# TeensySensor20250629.net
KiCad netlist of a schematic drawn in EasyEDA Pro
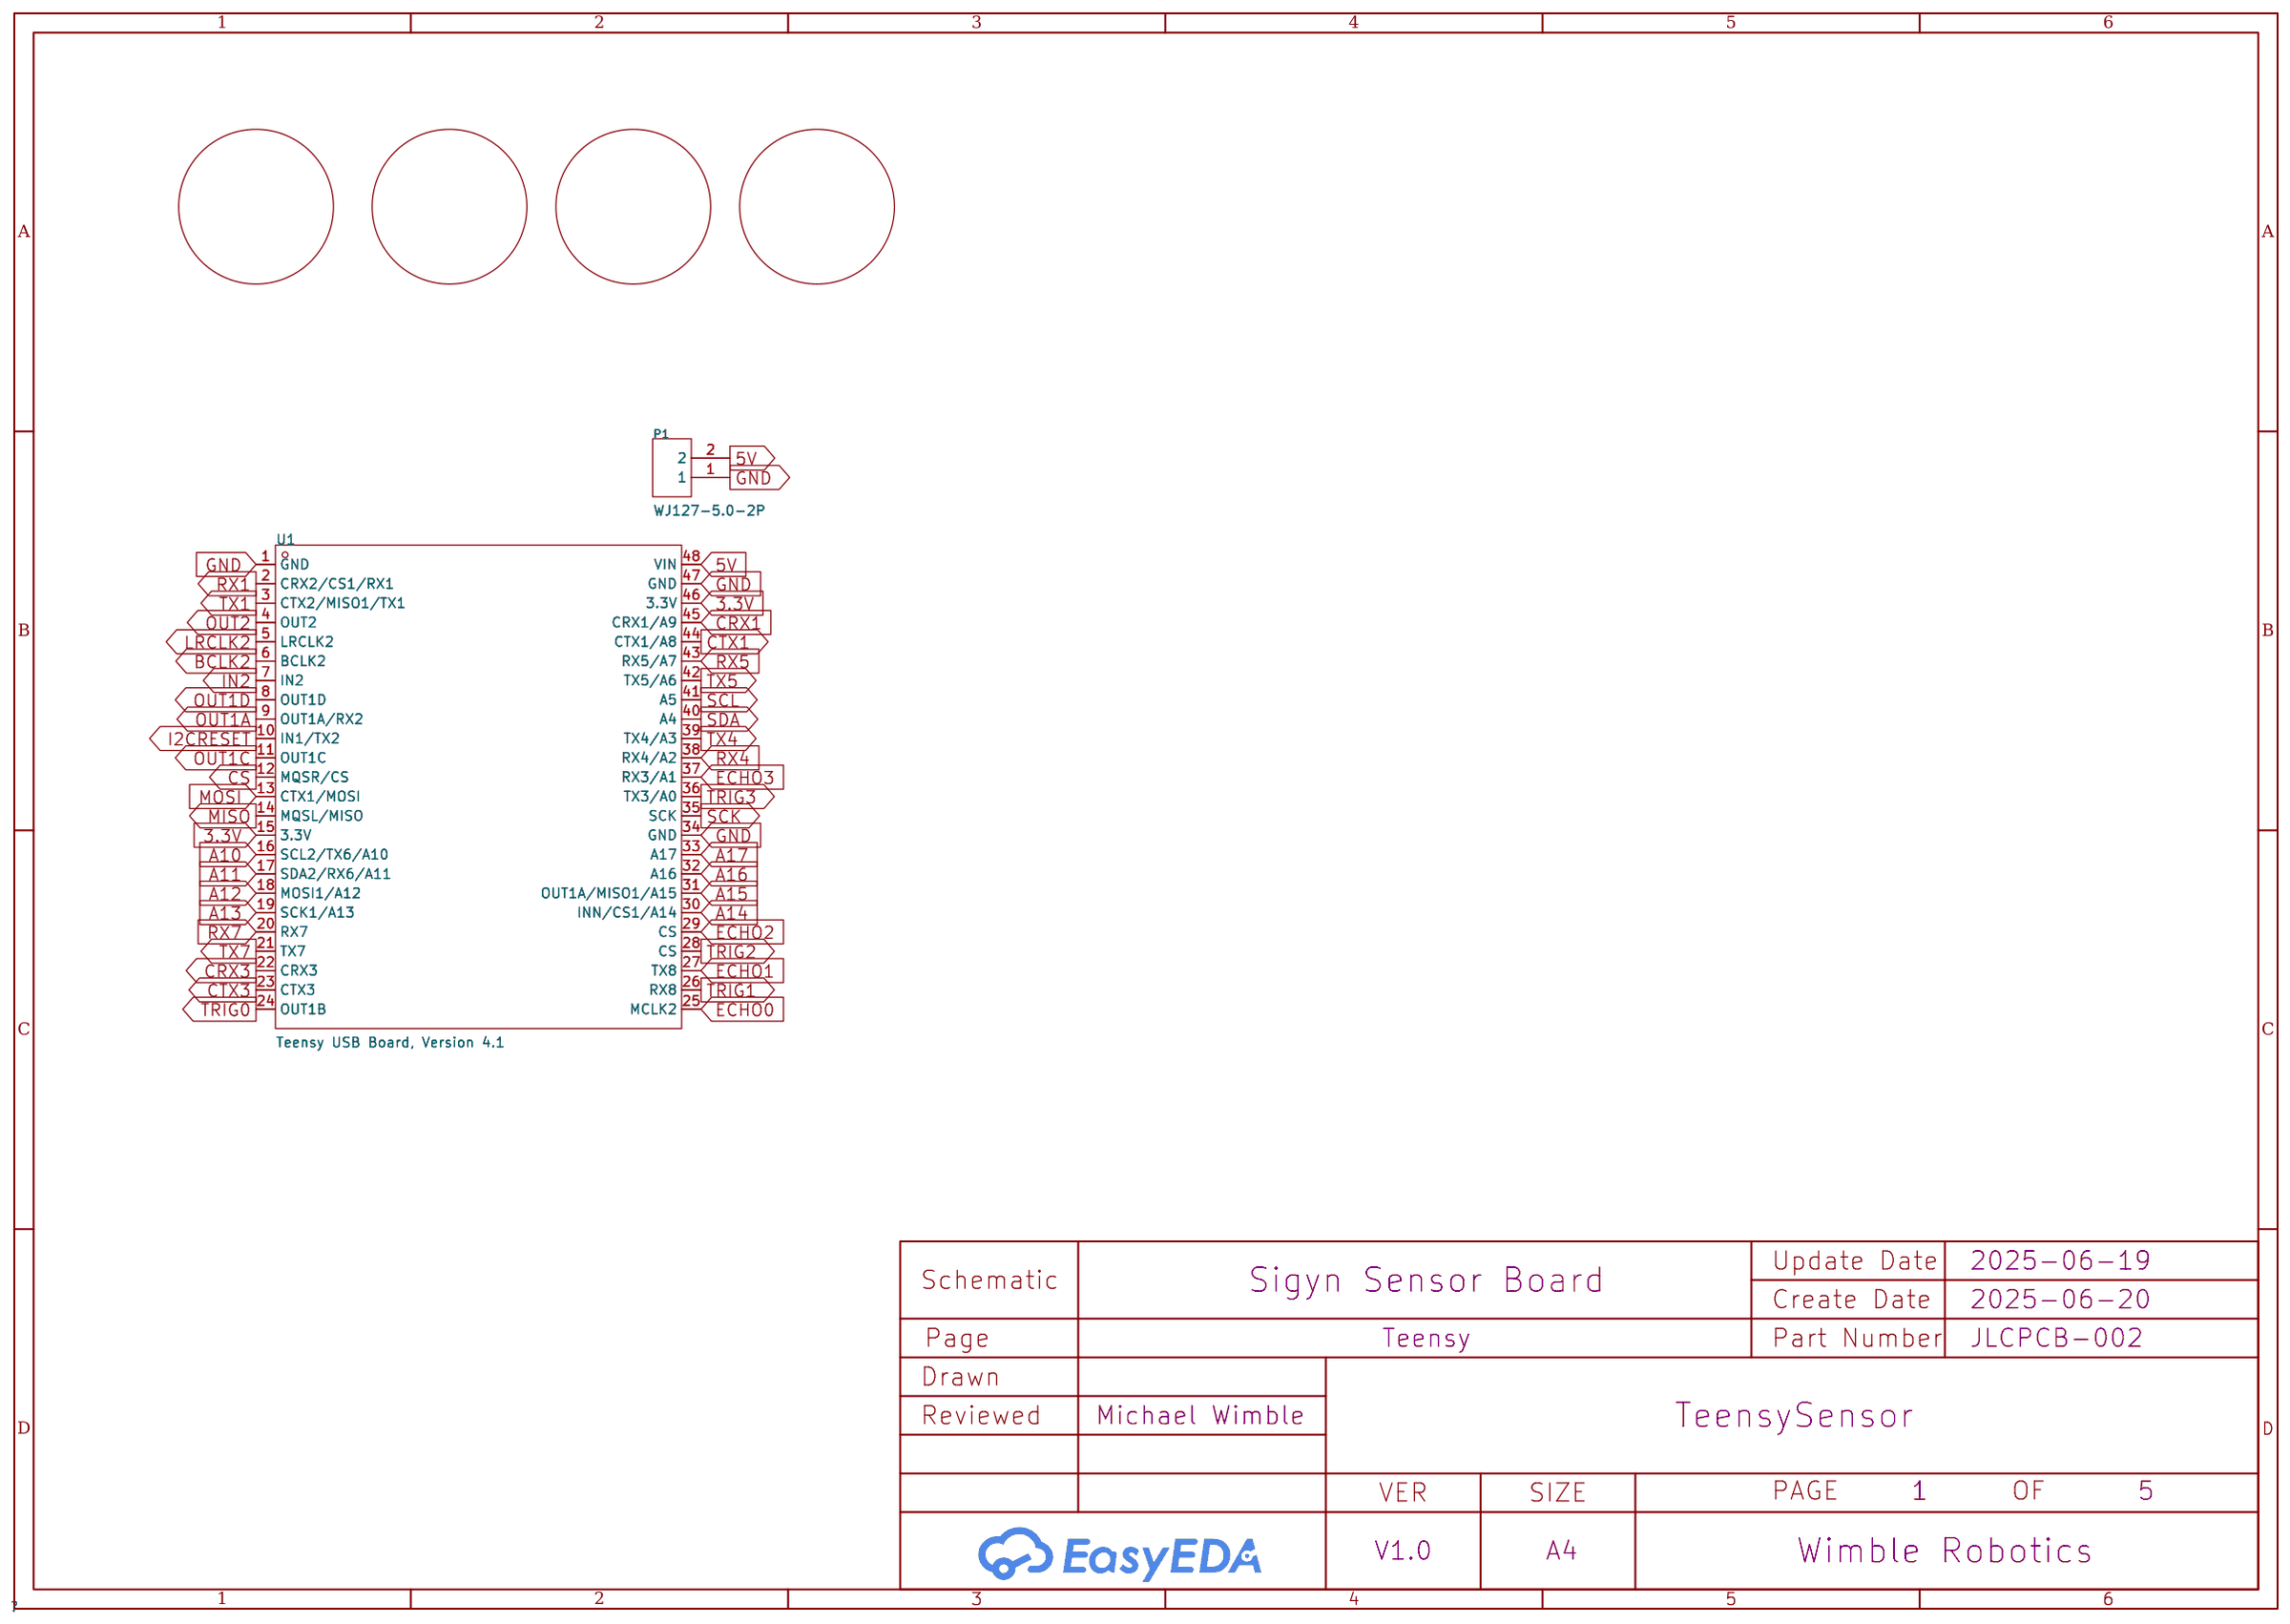
[diagram p0: Teensy]
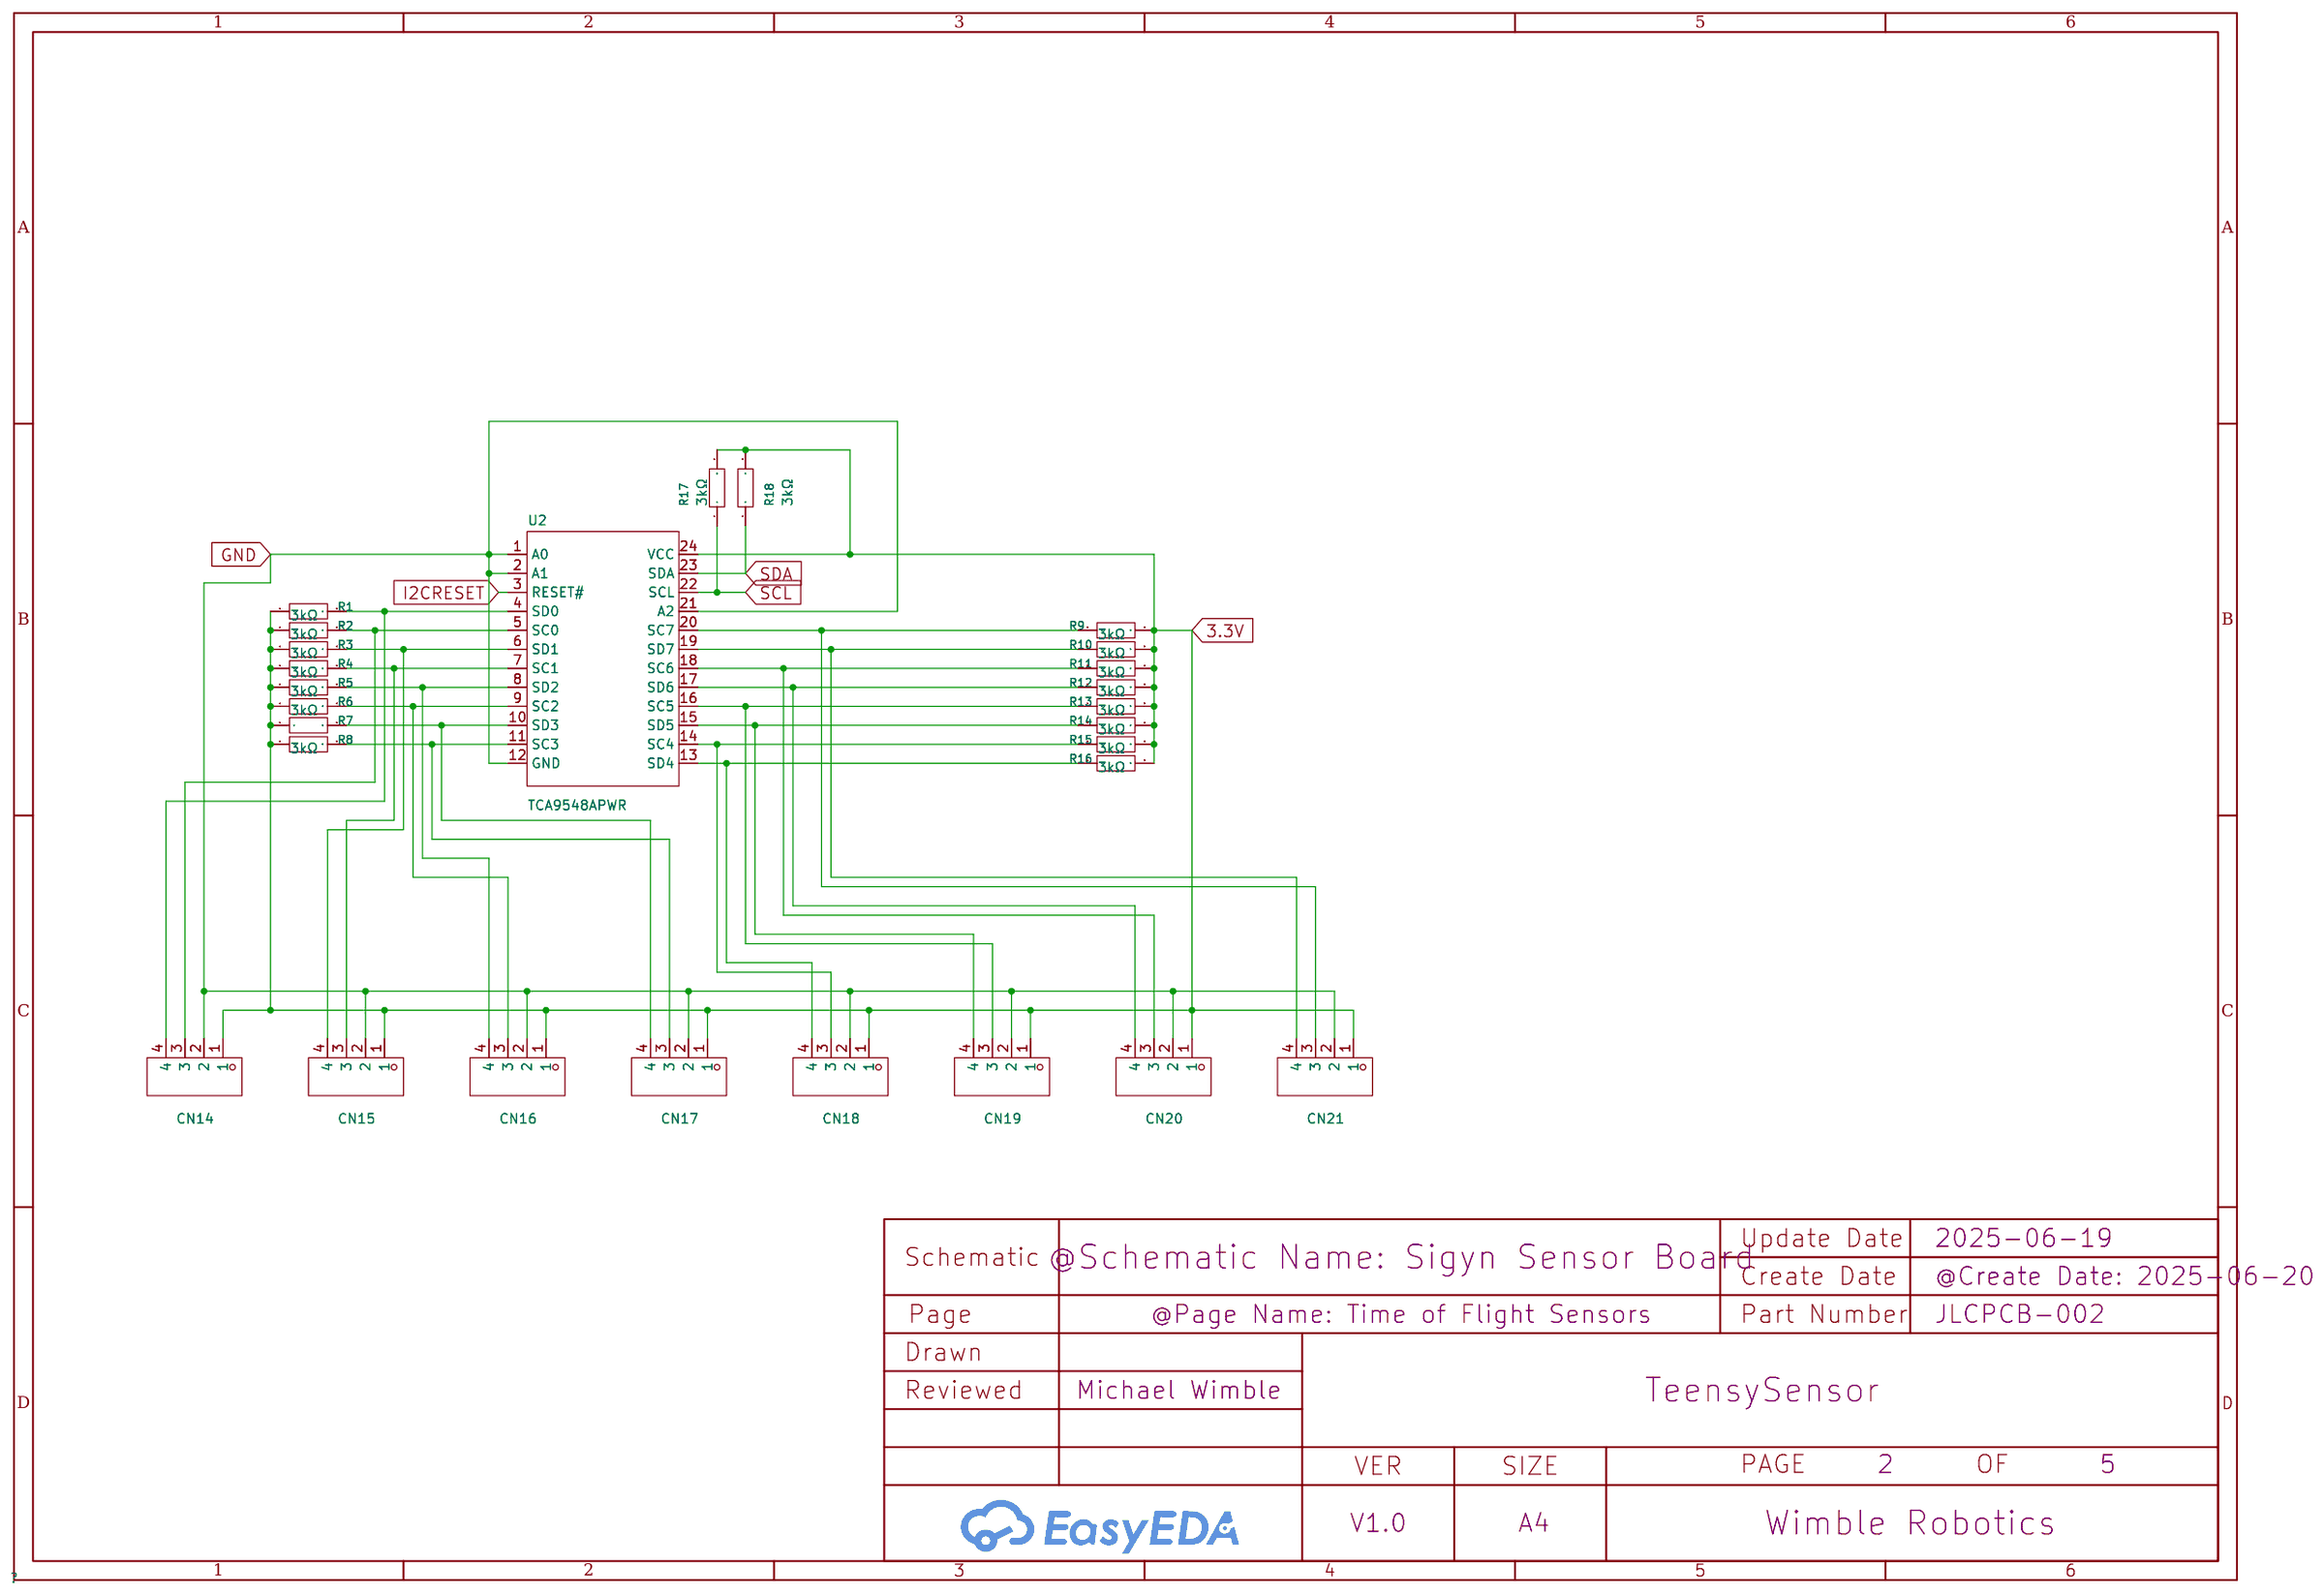
[diagram p1: Time of Flight Sensors]
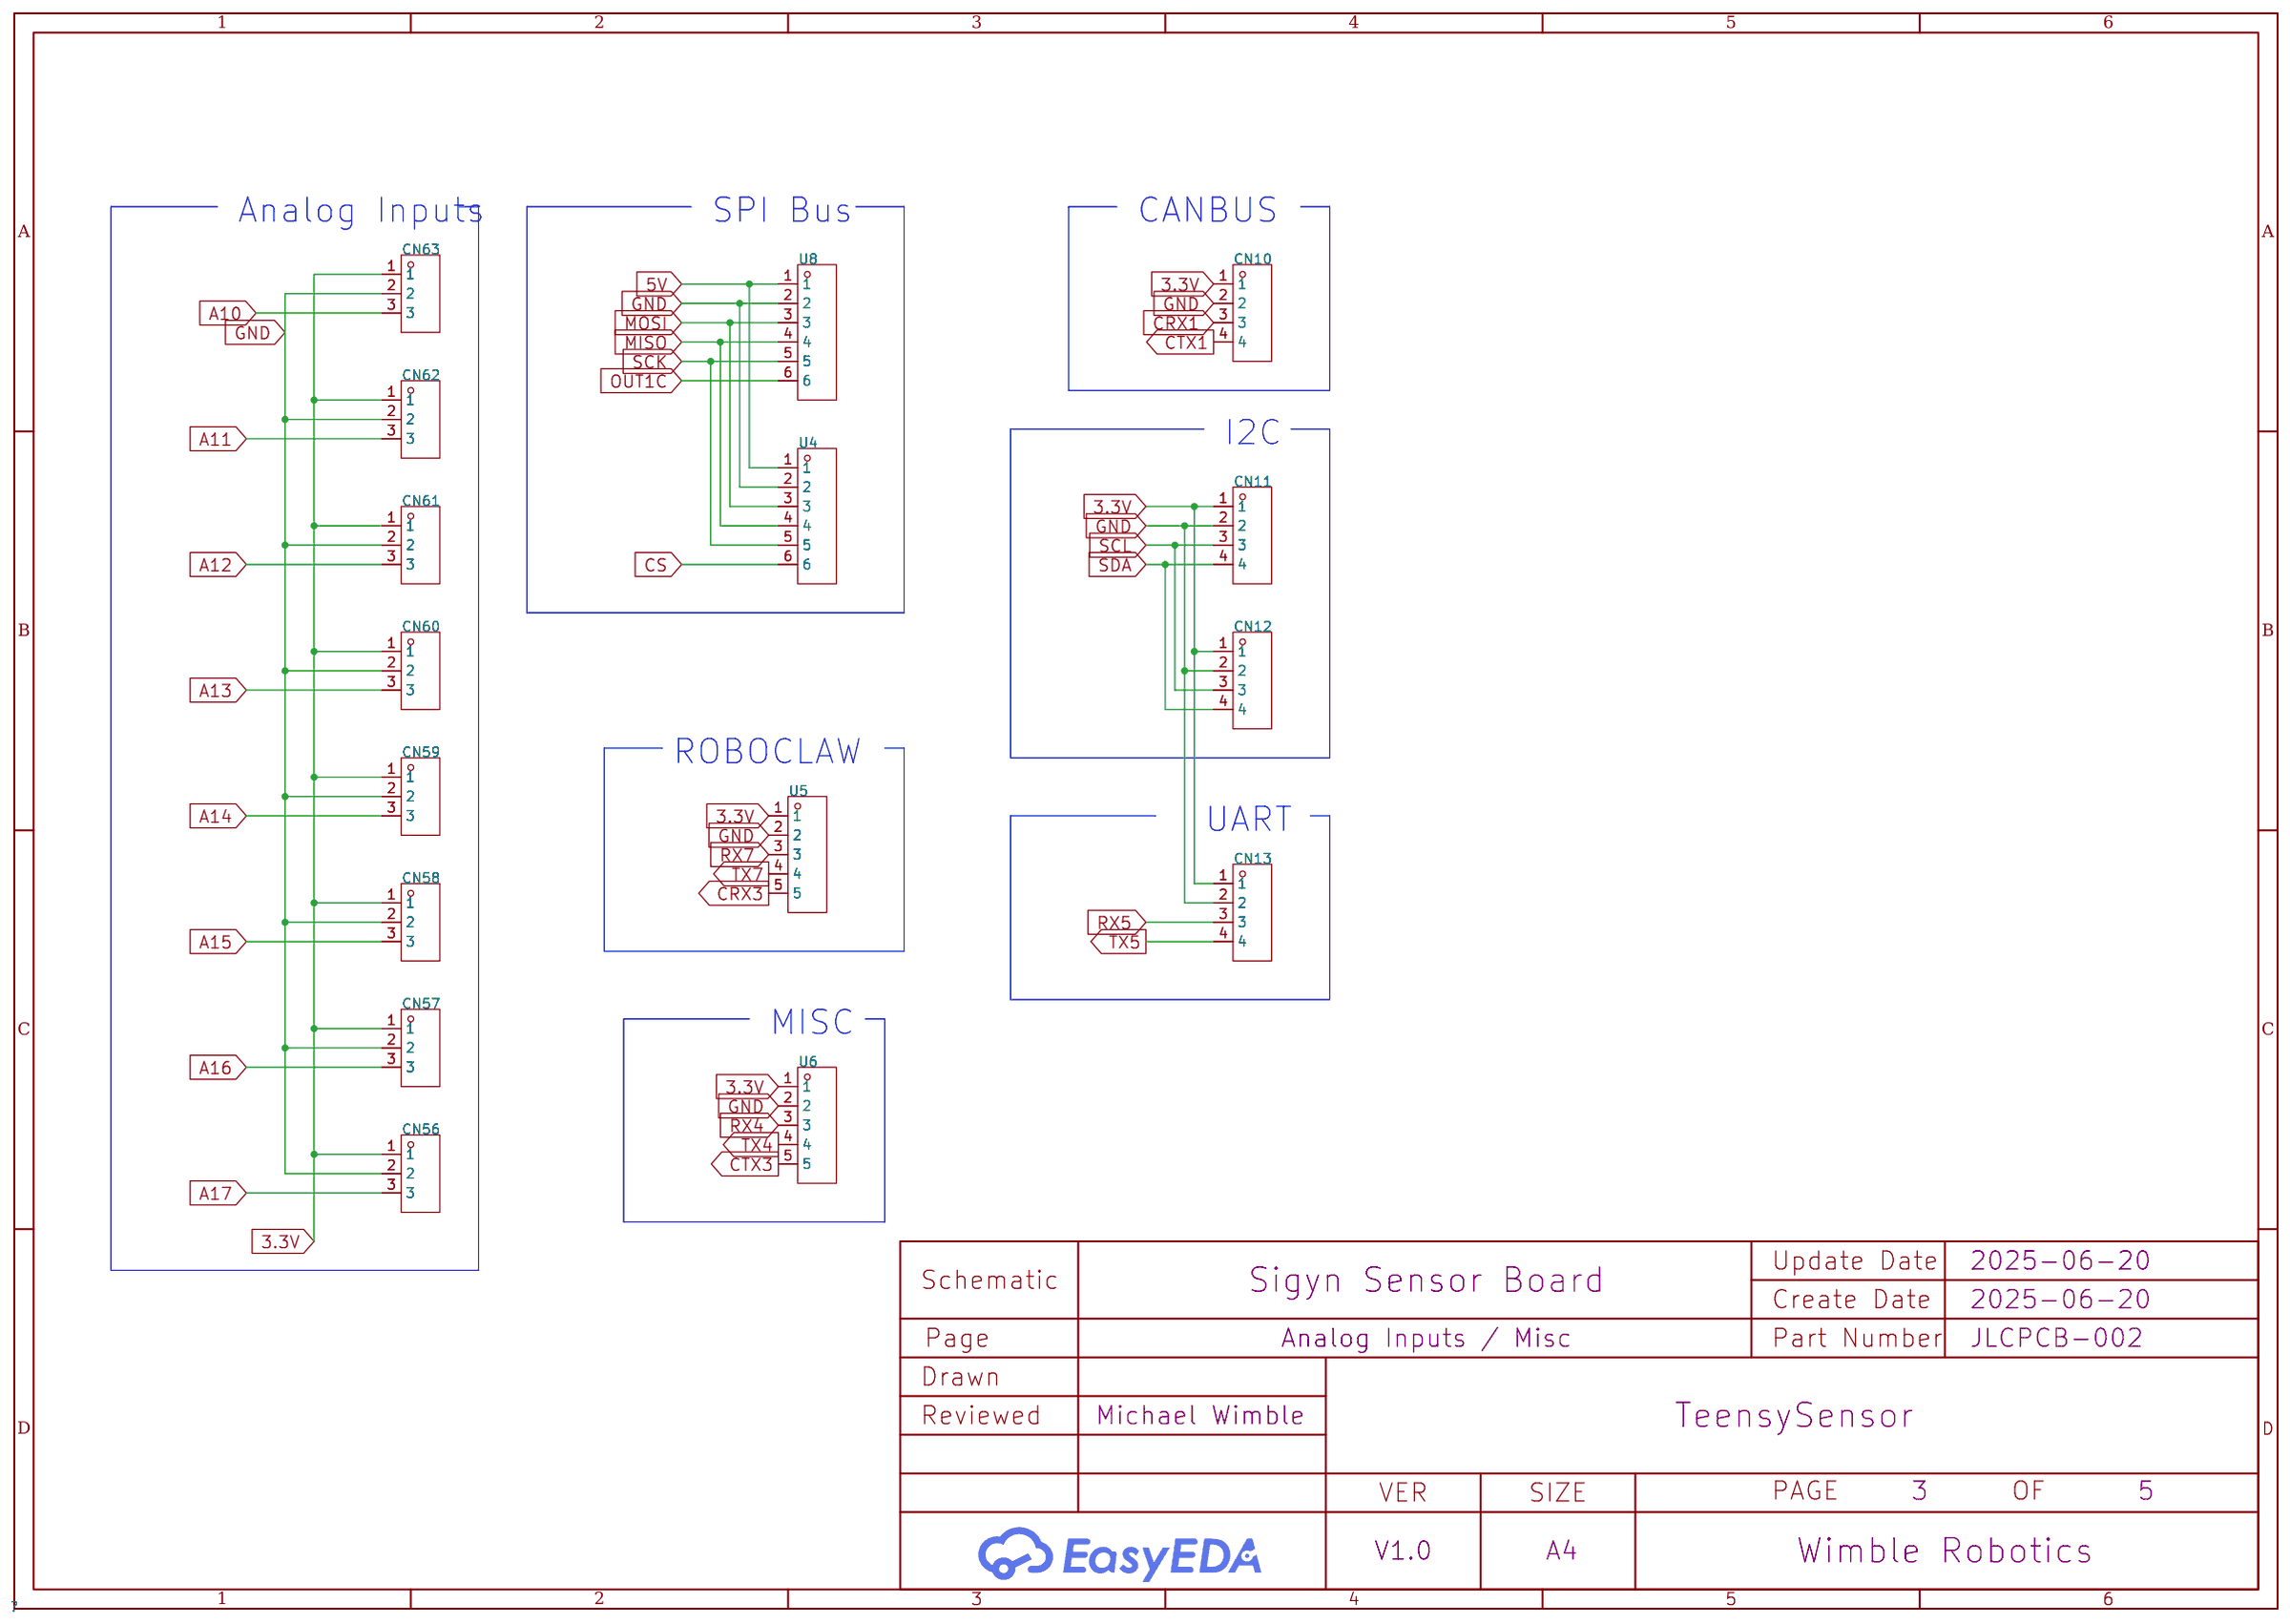
[diagram p2: Analog Inputs / Misc]
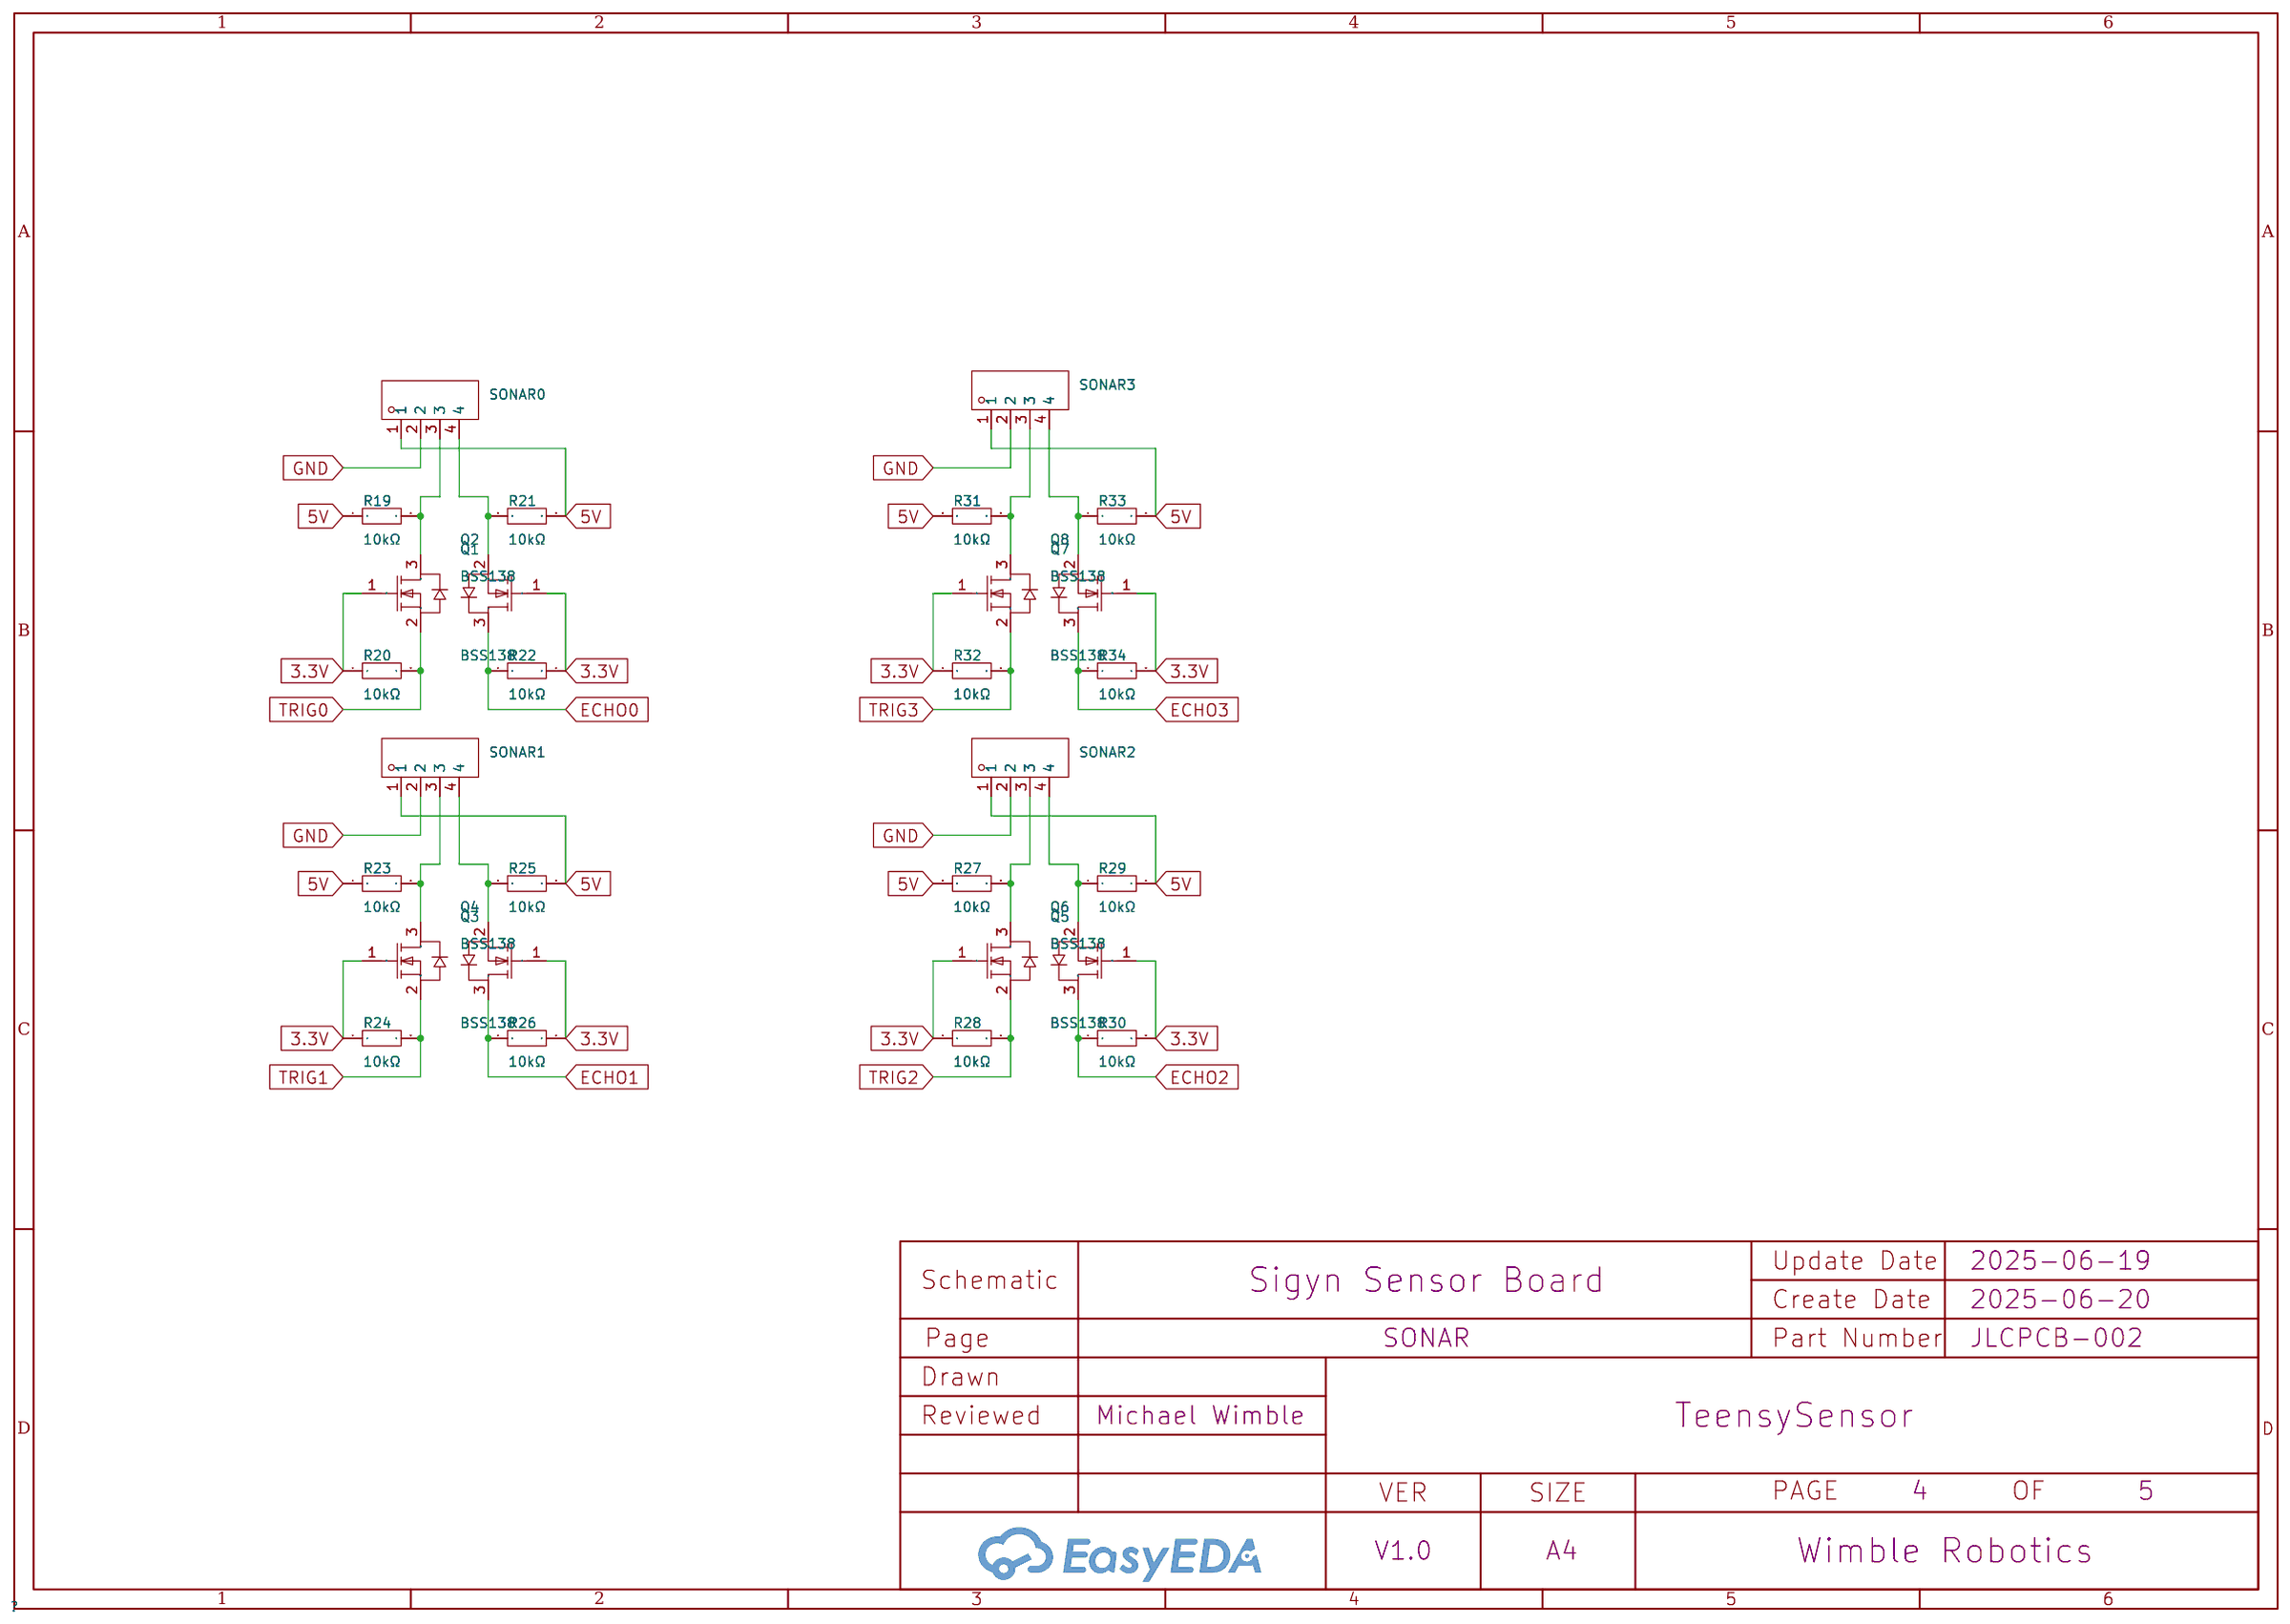
[diagram p3: SONAR]
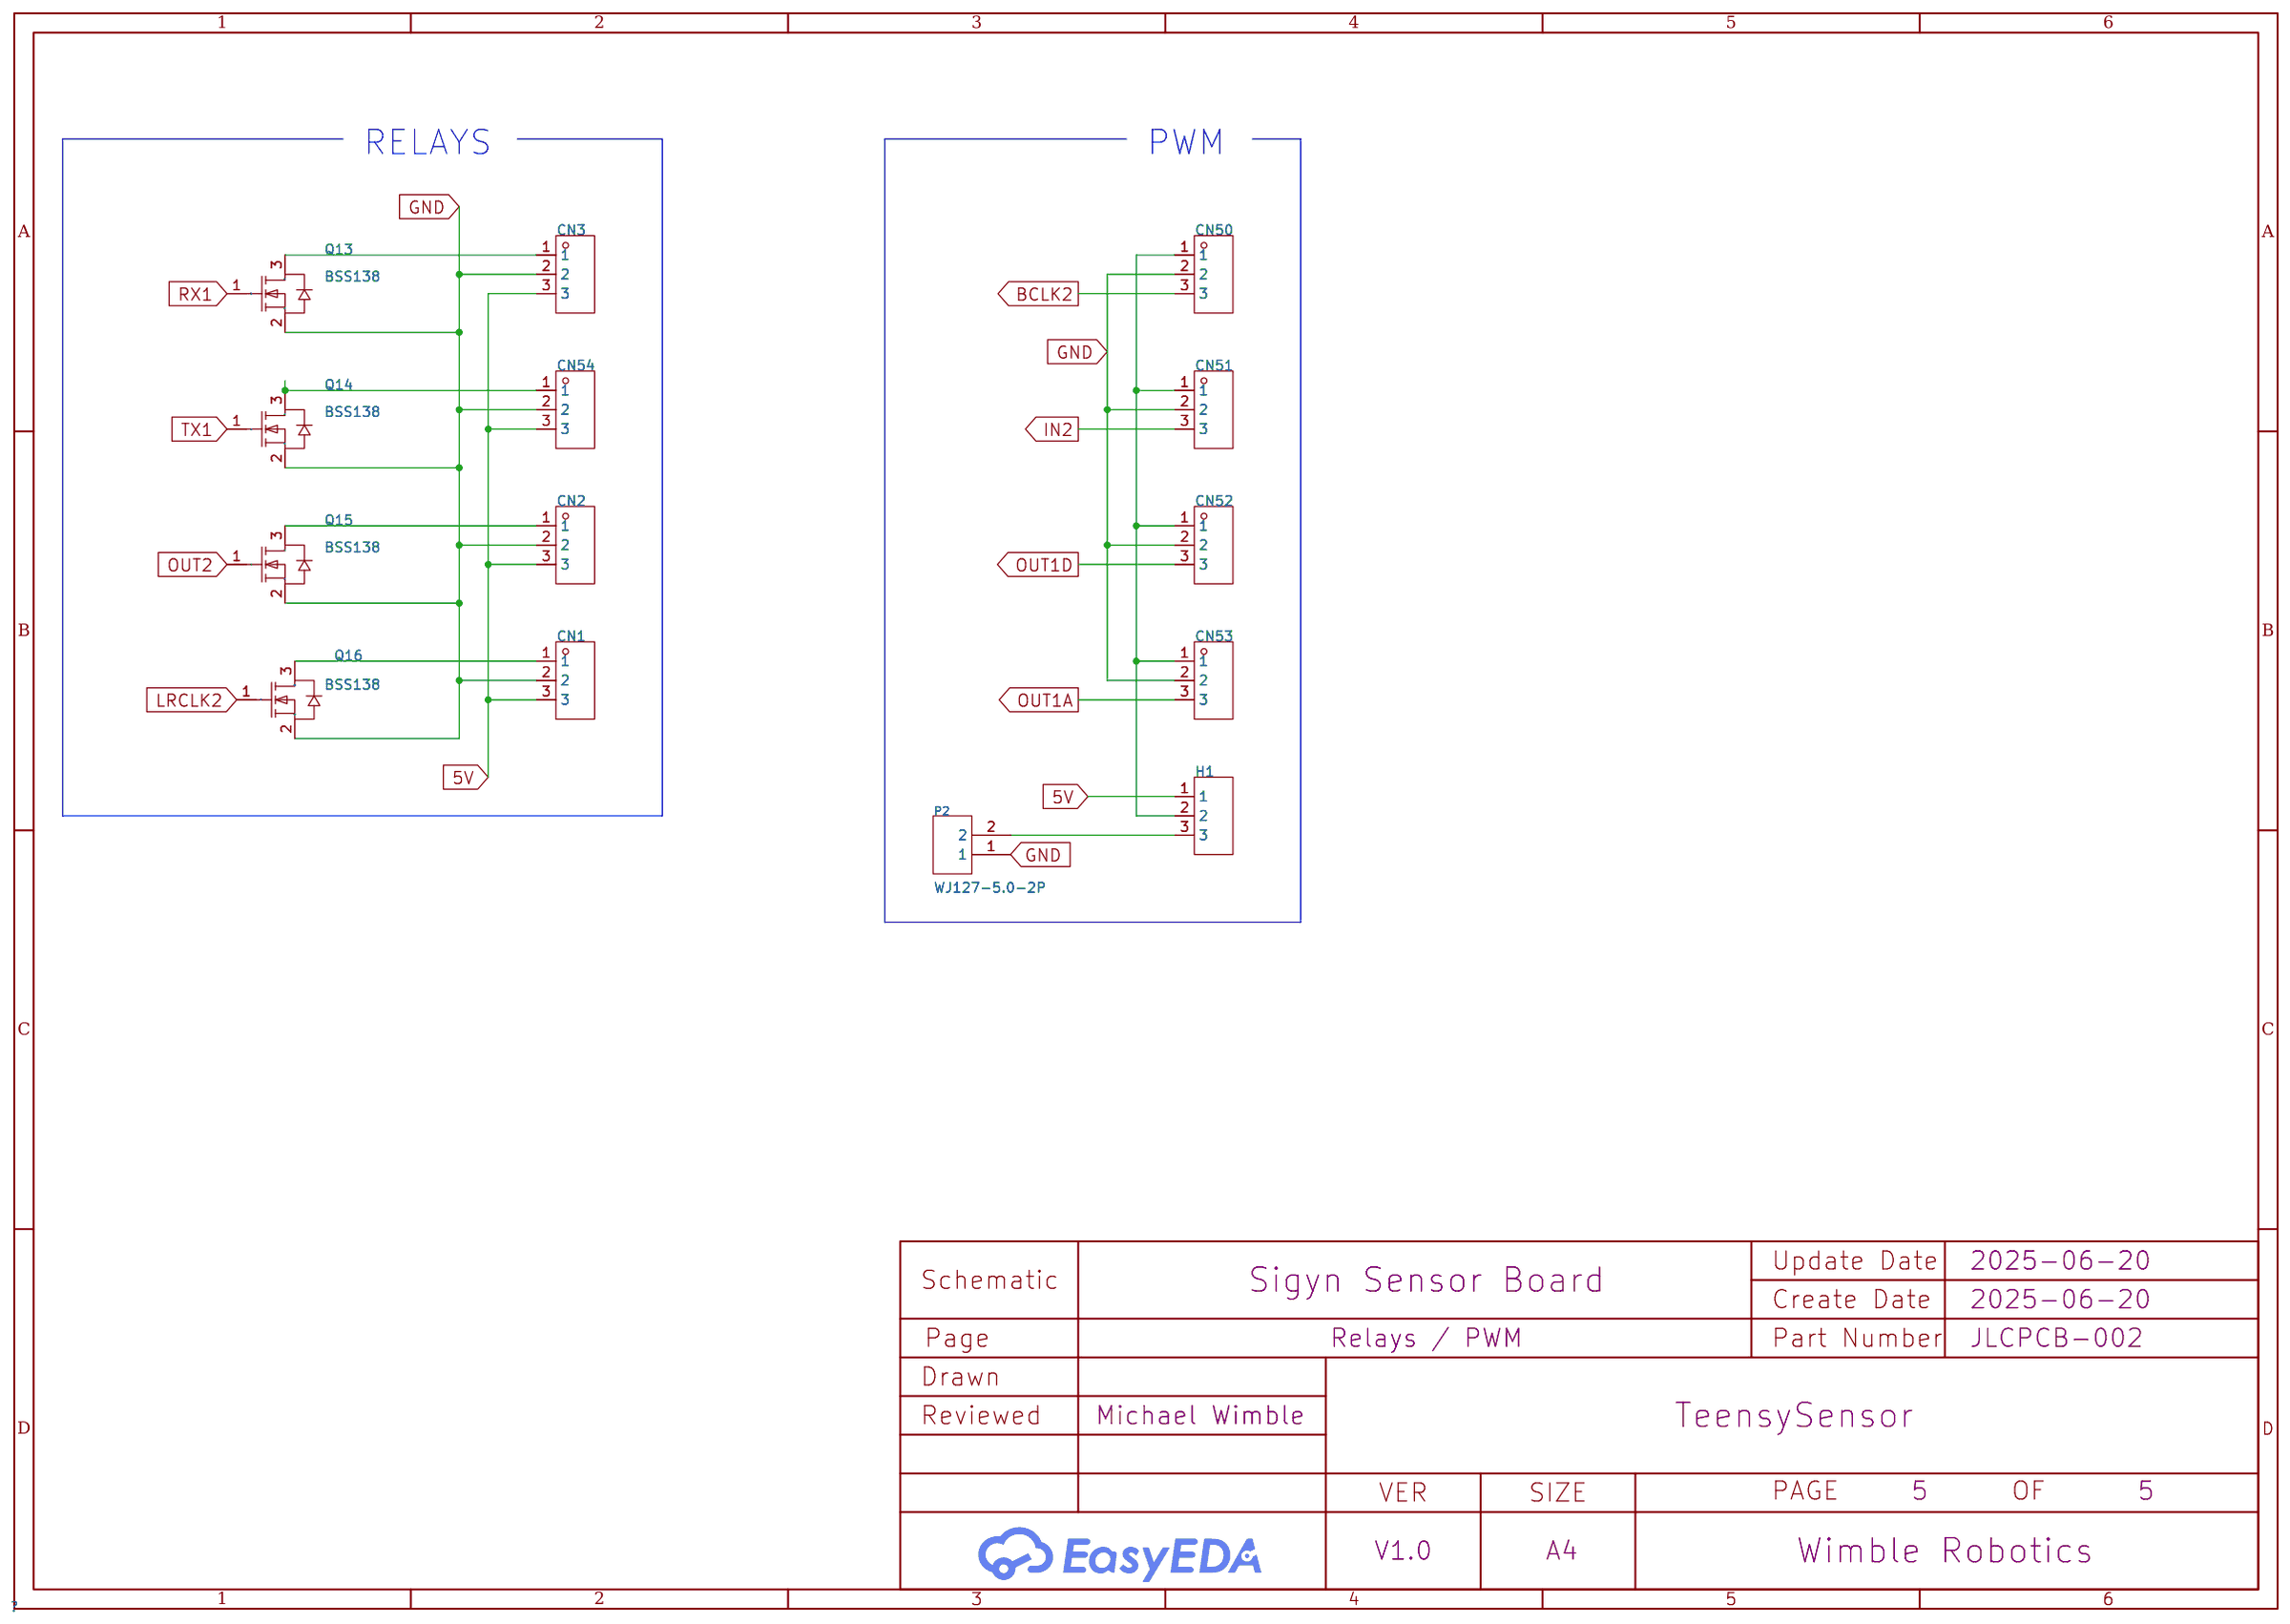
[diagram p4: Relays / PWM]

(export (version "E")
  (design (tool "Eeschema 10.0.6"))
  (components
    (comp (ref "P1")
      (value "WJ127-5.0-2P")
      (footprint "easyedapro:CONN-TH_2P-P5.00_CPC3703CTR")
      (fields (field (name "Manufacturer") "KANGNEX(康奈克斯电气)"))
      (libsource (lib "easyedapro") (part "WJ127-5.0-2P"))
    )
    (comp (ref "U1")
      (value "Teensy USB Board, Version 4.1")
      (footprint "easyedapro:COMM-TH_L61.0-W17.8-P2.54")
      (libsource (lib "easyedapro") (part "TEENSY USB BOARD, VERSION 4.1"))
    )
    (comp (ref "U12")
      (value "~")
      (footprint "easyedapro:3.5mm_Hole")
      (description "Mounting hole")
      (libsource (lib "easyedapro") (part "3.5MMHole"))
    )
    (comp (ref "U13")
      (value "~")
      (footprint "easyedapro:3.5mm_Hole")
      (description "Mounting hole")
      (libsource (lib "easyedapro") (part "3.5MMHole"))
    )
    (comp (ref "U14")
      (value "~")
      (footprint "easyedapro:3.5mm_Hole")
      (description "Mounting hole")
      (libsource (lib "easyedapro") (part "3.5MMHole"))
    )
    (comp (ref "U15")
      (value "~")
      (footprint "easyedapro:3.5mm_Hole")
      (description "Mounting hole")
      (libsource (lib "easyedapro") (part "3.5MMHole"))
    )
    (comp (ref "CN14")
      (value "ZX-XH2.54-4PZZ")
      (footprint "easyedapro:CONN-TH_4P-P2.50_4PIN")
      (fields (field (name "Manufacturer") "Megastar(兆星)"))
      (libsource (lib "easyedapro") (part "ZX-XH2.54-4PZZ"))
    )
    (comp (ref "CN15")
      (value "ZX-XH2.54-4PZZ")
      (footprint "easyedapro:CONN-TH_4P-P2.50_4PIN")
      (fields (field (name "Manufacturer") "Megastar(兆星)"))
      (libsource (lib "easyedapro") (part "ZX-XH2.54-4PZZ"))
    )
    (comp (ref "CN16")
      (value "ZX-XH2.54-4PZZ")
      (footprint "easyedapro:CONN-TH_4P-P2.50_4PIN")
      (fields (field (name "Manufacturer") "Megastar(兆星)"))
      (libsource (lib "easyedapro") (part "ZX-XH2.54-4PZZ"))
    )
    (comp (ref "CN17")
      (value "ZX-XH2.54-4PZZ")
      (footprint "easyedapro:CONN-TH_4P-P2.50_4PIN")
      (fields (field (name "Manufacturer") "Megastar(兆星)"))
      (libsource (lib "easyedapro") (part "ZX-XH2.54-4PZZ"))
    )
    (comp (ref "CN18")
      (value "ZX-XH2.54-4PZZ")
      (footprint "easyedapro:CONN-TH_4P-P2.50_4PIN")
      (fields (field (name "Manufacturer") "Megastar(兆星)"))
      (libsource (lib "easyedapro") (part "ZX-XH2.54-4PZZ"))
    )
    (comp (ref "CN19")
      (value "ZX-XH2.54-4PZZ")
      (footprint "easyedapro:CONN-TH_4P-P2.50_4PIN")
      (fields (field (name "Manufacturer") "Megastar(兆星)"))
      (libsource (lib "easyedapro") (part "ZX-XH2.54-4PZZ"))
    )
    (comp (ref "CN20")
      (value "ZX-XH2.54-4PZZ")
      (footprint "easyedapro:CONN-TH_4P-P2.50_4PIN")
      (fields (field (name "Manufacturer") "Megastar(兆星)"))
      (libsource (lib "easyedapro") (part "ZX-XH2.54-4PZZ"))
    )
    (comp (ref "CN21")
      (value "ZX-XH2.54-4PZZ")
      (footprint "easyedapro:CONN-TH_4P-P2.50_4PIN")
      (fields (field (name "Manufacturer") "Megastar(兆星)"))
      (libsource (lib "easyedapro") (part "ZX-XH2.54-4PZZ"))
    )
    (comp (ref "R1")
      (value "3kΩ")
      (footprint "easyedapro:R0603")
      (fields
        (field (name "Manufacturer Part") "0603WAF3001T5E")
        (field (name "Manufacturer") "UNI-ROYAL(厚声)")
      )
      (libsource (lib "easyedapro") (part "0603WAF3001T5E"))
    )
    (comp (ref "R2")
      (value "3kΩ")
      (footprint "easyedapro:R0603")
      (fields
        (field (name "Manufacturer Part") "0603WAF3001T5E")
        (field (name "Manufacturer") "UNI-ROYAL(厚声)")
      )
      (libsource (lib "easyedapro") (part "0603WAF3001T5E"))
    )
    (comp (ref "R3")
      (value "3kΩ")
      (footprint "easyedapro:R0603")
      (fields
        (field (name "Manufacturer Part") "0603WAF3001T5E")
        (field (name "Manufacturer") "UNI-ROYAL(厚声)")
      )
      (libsource (lib "easyedapro") (part "0603WAF3001T5E"))
    )
    (comp (ref "R4")
      (value "3kΩ")
      (footprint "easyedapro:R0603")
      (fields
        (field (name "Manufacturer Part") "0603WAF3001T5E")
        (field (name "Manufacturer") "UNI-ROYAL(厚声)")
      )
      (libsource (lib "easyedapro") (part "0603WAF3001T5E"))
    )
    (comp (ref "R5")
      (value "3kΩ")
      (footprint "easyedapro:R0603")
      (fields
        (field (name "Manufacturer Part") "0603WAF3001T5E")
        (field (name "Manufacturer") "UNI-ROYAL(厚声)")
      )
      (libsource (lib "easyedapro") (part "0603WAF3001T5E"))
    )
    (comp (ref "R6")
      (value "3kΩ")
      (footprint "easyedapro:R0603")
      (fields
        (field (name "Manufacturer Part") "0603WAF3001T5E")
        (field (name "Manufacturer") "UNI-ROYAL(厚声)")
      )
      (libsource (lib "easyedapro") (part "0603WAF3001T5E"))
    )
    (comp (ref "R7")
      (value "3kΩ")
      (footprint "easyedapro:R0603")
      (fields
        (field (name "Manufacturer Part") "0603WAF3001T5E")
        (field (name "Manufacturer") "UNI-ROYAL(厚声)")
      )
      (libsource (lib "easyedapro") (part "0603WAF3001T5E"))
    )
    (comp (ref "R8")
      (value "3kΩ")
      (footprint "easyedapro:R0603")
      (fields
        (field (name "Manufacturer Part") "0603WAF3001T5E")
        (field (name "Manufacturer") "UNI-ROYAL(厚声)")
      )
      (libsource (lib "easyedapro") (part "0603WAF3001T5E"))
    )
    (comp (ref "R9")
      (value "3kΩ")
      (footprint "easyedapro:R0603")
      (fields
        (field (name "Manufacturer Part") "0603WAF3001T5E")
        (field (name "Manufacturer") "UNI-ROYAL(厚声)")
      )
      (libsource (lib "easyedapro") (part "0603WAF3001T5E"))
    )
    (comp (ref "R10")
      (value "3kΩ")
      (footprint "easyedapro:R0603")
      (fields
        (field (name "Manufacturer Part") "0603WAF3001T5E")
        (field (name "Manufacturer") "UNI-ROYAL(厚声)")
      )
      (libsource (lib "easyedapro") (part "0603WAF3001T5E"))
    )
    (comp (ref "R11")
      (value "3kΩ")
      (footprint "easyedapro:R0603")
      (fields
        (field (name "Manufacturer Part") "0603WAF3001T5E")
        (field (name "Manufacturer") "UNI-ROYAL(厚声)")
      )
      (libsource (lib "easyedapro") (part "0603WAF3001T5E"))
    )
    (comp (ref "R12")
      (value "3kΩ")
      (footprint "easyedapro:R0603")
      (fields
        (field (name "Manufacturer Part") "0603WAF3001T5E")
        (field (name "Manufacturer") "UNI-ROYAL(厚声)")
      )
      (libsource (lib "easyedapro") (part "0603WAF3001T5E"))
    )
    (comp (ref "R13")
      (value "3kΩ")
      (footprint "easyedapro:R0603")
      (fields
        (field (name "Manufacturer Part") "0603WAF3001T5E")
        (field (name "Manufacturer") "UNI-ROYAL(厚声)")
      )
      (libsource (lib "easyedapro") (part "0603WAF3001T5E"))
    )
    (comp (ref "R14")
      (value "3kΩ")
      (footprint "easyedapro:R0603")
      (fields
        (field (name "Manufacturer Part") "0603WAF3001T5E")
        (field (name "Manufacturer") "UNI-ROYAL(厚声)")
      )
      (libsource (lib "easyedapro") (part "0603WAF3001T5E"))
    )
    (comp (ref "R15")
      (value "3kΩ")
      (footprint "easyedapro:R0603")
      (fields
        (field (name "Manufacturer Part") "0603WAF3001T5E")
        (field (name "Manufacturer") "UNI-ROYAL(厚声)")
      )
      (libsource (lib "easyedapro") (part "0603WAF3001T5E"))
    )
    (comp (ref "R16")
      (value "3kΩ")
      (footprint "easyedapro:R0603")
      (fields
        (field (name "Manufacturer Part") "0603WAF3001T5E")
        (field (name "Manufacturer") "UNI-ROYAL(厚声)")
      )
      (libsource (lib "easyedapro") (part "0603WAF3001T5E"))
    )
    (comp (ref "R17")
      (value "3kΩ")
      (footprint "easyedapro:R0603")
      (fields
        (field (name "Manufacturer Part") "0603WAF3001T5E")
        (field (name "Manufacturer") "UNI-ROYAL(厚声)")
      )
      (libsource (lib "easyedapro") (part "0603WAF3001T5E"))
    )
    (comp (ref "R18")
      (value "3kΩ")
      (footprint "easyedapro:R0603")
      (fields
        (field (name "Manufacturer Part") "0603WAF3001T5E")
        (field (name "Manufacturer") "UNI-ROYAL(厚声)")
      )
      (libsource (lib "easyedapro") (part "0603WAF3001T5E"))
    )
    (comp (ref "U2")
      (value "TCA9548APWR")
      (footprint "easyedapro:TSSOP-24_L7.8-W4.4-P0.65-LS6.4-BL")
      (fields (field (name "Manufacturer") "TI(德州仪器)"))
      (libsource (lib "easyedapro") (part "TCA9548APWR"))
    )
    (comp (ref "CN10")
      (value "ZX-XH2.54-4PZZ")
      (footprint "easyedapro:CONN-TH_4P-P2.50_4PIN")
      (fields (field (name "Manufacturer") "Megastar(兆星)"))
      (libsource (lib "easyedapro") (part "ZX-XH2.54-4PZZ"))
    )
    (comp (ref "CN11")
      (value "ZX-XH2.54-4PZZ")
      (footprint "easyedapro:CONN-TH_4P-P2.50_4PIN")
      (fields (field (name "Manufacturer") "Megastar(兆星)"))
      (libsource (lib "easyedapro") (part "ZX-XH2.54-4PZZ"))
    )
    (comp (ref "CN12")
      (value "ZX-XH2.54-4PZZ")
      (footprint "easyedapro:CONN-TH_4P-P2.50_4PIN")
      (fields (field (name "Manufacturer") "Megastar(兆星)"))
      (libsource (lib "easyedapro") (part "ZX-XH2.54-4PZZ"))
    )
    (comp (ref "CN13")
      (value "ZX-XH2.54-4PZZ")
      (footprint "easyedapro:CONN-TH_4P-P2.50_4PIN")
      (fields (field (name "Manufacturer") "Megastar(兆星)"))
      (libsource (lib "easyedapro") (part "ZX-XH2.54-4PZZ"))
    )
    (comp (ref "CN56")
      (value "ZX-XH2.54-3PZZ")
      (footprint "easyedapro:CONN-TH_3P-P2.54_2501S-3P")
      (fields (field (name "Manufacturer") "Megastar(兆星)"))
      (libsource (lib "easyedapro") (part "ZX-XH2.54-3PZZ"))
    )
    (comp (ref "CN57")
      (value "ZX-XH2.54-3PZZ")
      (footprint "easyedapro:CONN-TH_3P-P2.54_2501S-3P")
      (fields (field (name "Manufacturer") "Megastar(兆星)"))
      (libsource (lib "easyedapro") (part "ZX-XH2.54-3PZZ"))
    )
    (comp (ref "CN58")
      (value "ZX-XH2.54-3PZZ")
      (footprint "easyedapro:CONN-TH_3P-P2.54_2501S-3P")
      (fields (field (name "Manufacturer") "Megastar(兆星)"))
      (libsource (lib "easyedapro") (part "ZX-XH2.54-3PZZ"))
    )
    (comp (ref "CN59")
      (value "ZX-XH2.54-3PZZ")
      (footprint "easyedapro:CONN-TH_3P-P2.54_2501S-3P")
      (fields (field (name "Manufacturer") "Megastar(兆星)"))
      (libsource (lib "easyedapro") (part "ZX-XH2.54-3PZZ"))
    )
    (comp (ref "CN60")
      (value "ZX-XH2.54-3PZZ")
      (footprint "easyedapro:CONN-TH_3P-P2.54_2501S-3P")
      (fields (field (name "Manufacturer") "Megastar(兆星)"))
      (libsource (lib "easyedapro") (part "ZX-XH2.54-3PZZ"))
    )
    (comp (ref "CN61")
      (value "ZX-XH2.54-3PZZ")
      (footprint "easyedapro:CONN-TH_3P-P2.54_2501S-3P")
      (fields (field (name "Manufacturer") "Megastar(兆星)"))
      (libsource (lib "easyedapro") (part "ZX-XH2.54-3PZZ"))
    )
    (comp (ref "CN62")
      (value "ZX-XH2.54-3PZZ")
      (footprint "easyedapro:CONN-TH_3P-P2.54_2501S-3P")
      (fields (field (name "Manufacturer") "Megastar(兆星)"))
      (libsource (lib "easyedapro") (part "ZX-XH2.54-3PZZ"))
    )
    (comp (ref "CN63")
      (value "ZX-XH2.54-3PZZ")
      (footprint "easyedapro:CONN-TH_3P-P2.54_2501S-3P")
      (fields (field (name "Manufacturer") "Megastar(兆星)"))
      (libsource (lib "easyedapro") (part "ZX-XH2.54-3PZZ"))
    )
    (comp (ref "U4")
      (value "ZX-XH2.54-6PZZ")
      (footprint "easyedapro:CONN-TH_6P-P2.50_ZX-XH2.54-6PZZ")
      (fields (field (name "Manufacturer") "Megastar(兆星)"))
      (libsource (lib "easyedapro") (part "ZX-XH2.54-6PZZ"))
    )
    (comp (ref "U5")
      (value "ZX-XH2.54-5PZZ")
      (footprint "easyedapro:CONN-TH_5P-P2.50_ZX-XH2.54-5PZZ")
      (fields (field (name "Manufacturer") "Megastar(兆星)"))
      (libsource (lib "easyedapro") (part "ZX-XH2.54-5PZZ"))
    )
    (comp (ref "U6")
      (value "ZX-XH2.54-5PZZ")
      (footprint "easyedapro:CONN-TH_5P-P2.50_ZX-XH2.54-5PZZ")
      (fields (field (name "Manufacturer") "Megastar(兆星)"))
      (libsource (lib "easyedapro") (part "ZX-XH2.54-5PZZ"))
    )
    (comp (ref "U8")
      (value "ZX-XH2.54-6PZZ")
      (footprint "easyedapro:CONN-TH_6P-P2.50_ZX-XH2.54-6PZZ")
      (fields (field (name "Manufacturer") "Megastar(兆星)"))
      (libsource (lib "easyedapro") (part "ZX-XH2.54-6PZZ"))
    )
    (comp (ref "Q1")
      (value "BSS138")
      (footprint "easyedapro:SOT-23-3_L2.9-W1.6-P1.90-LS2.8-BR")
      (fields (field (name "Manufacturer") "TECH PUBLIC(台舟)"))
      (libsource (lib "easyedapro") (part "BSS138_C18212695"))
    )
    (comp (ref "Q2")
      (value "BSS138")
      (footprint "easyedapro:SOT-23-3_L2.9-W1.6-P1.90-LS2.8-BR")
      (fields (field (name "Manufacturer") "TECH PUBLIC(台舟)"))
      (libsource (lib "easyedapro") (part "BSS138_C18212695"))
    )
    (comp (ref "Q3")
      (value "BSS138")
      (footprint "easyedapro:SOT-23-3_L2.9-W1.6-P1.90-LS2.8-BR")
      (fields (field (name "Manufacturer") "TECH PUBLIC(台舟)"))
      (libsource (lib "easyedapro") (part "BSS138_C18212695"))
    )
    (comp (ref "Q4")
      (value "BSS138")
      (footprint "easyedapro:SOT-23-3_L2.9-W1.6-P1.90-LS2.8-BR")
      (fields (field (name "Manufacturer") "TECH PUBLIC(台舟)"))
      (libsource (lib "easyedapro") (part "BSS138_C18212695"))
    )
    (comp (ref "Q5")
      (value "BSS138")
      (footprint "easyedapro:SOT-23-3_L2.9-W1.6-P1.90-LS2.8-BR")
      (fields (field (name "Manufacturer") "TECH PUBLIC(台舟)"))
      (libsource (lib "easyedapro") (part "BSS138_C18212695"))
    )
    (comp (ref "Q6")
      (value "BSS138")
      (footprint "easyedapro:SOT-23-3_L2.9-W1.6-P1.90-LS2.8-BR")
      (fields (field (name "Manufacturer") "TECH PUBLIC(台舟)"))
      (libsource (lib "easyedapro") (part "BSS138_C18212695"))
    )
    (comp (ref "Q7")
      (value "BSS138")
      (footprint "easyedapro:SOT-23-3_L2.9-W1.6-P1.90-LS2.8-BR")
      (fields (field (name "Manufacturer") "TECH PUBLIC(台舟)"))
      (libsource (lib "easyedapro") (part "BSS138_C18212695"))
    )
    (comp (ref "Q8")
      (value "BSS138")
      (footprint "easyedapro:SOT-23-3_L2.9-W1.6-P1.90-LS2.8-BR")
      (fields (field (name "Manufacturer") "TECH PUBLIC(台舟)"))
      (libsource (lib "easyedapro") (part "BSS138_C18212695"))
    )
    (comp (ref "R19")
      (value "10kΩ")
      (footprint "easyedapro:R0603")
      (fields (field (name "Manufacturer Part") "RC0603FR-0710KL") (field (name "Manufacturer") "YAGEO(国巨)"))
      (libsource (lib "easyedapro") (part "RC0603FR-0710KL"))
    )
    (comp (ref "R20")
      (value "10kΩ")
      (footprint "easyedapro:R0603")
      (fields (field (name "Manufacturer Part") "RC0603FR-0710KL") (field (name "Manufacturer") "YAGEO(国巨)"))
      (libsource (lib "easyedapro") (part "RC0603FR-0710KL"))
    )
    (comp (ref "R21")
      (value "10kΩ")
      (footprint "easyedapro:R0603")
      (fields (field (name "Manufacturer Part") "RC0603FR-0710KL") (field (name "Manufacturer") "YAGEO(国巨)"))
      (libsource (lib "easyedapro") (part "RC0603FR-0710KL"))
    )
    (comp (ref "R22")
      (value "10kΩ")
      (footprint "easyedapro:R0603")
      (fields (field (name "Manufacturer Part") "RC0603FR-0710KL") (field (name "Manufacturer") "YAGEO(国巨)"))
      (libsource (lib "easyedapro") (part "RC0603FR-0710KL"))
    )
    (comp (ref "R23")
      (value "10kΩ")
      (footprint "easyedapro:R0603")
      (fields (field (name "Manufacturer Part") "RC0603FR-0710KL") (field (name "Manufacturer") "YAGEO(国巨)"))
      (libsource (lib "easyedapro") (part "RC0603FR-0710KL"))
    )
    (comp (ref "R24")
      (value "10kΩ")
      (footprint "easyedapro:R0603")
      (fields (field (name "Manufacturer Part") "RC0603FR-0710KL") (field (name "Manufacturer") "YAGEO(国巨)"))
      (libsource (lib "easyedapro") (part "RC0603FR-0710KL"))
    )
    (comp (ref "R25")
      (value "10kΩ")
      (footprint "easyedapro:R0603")
      (fields (field (name "Manufacturer Part") "RC0603FR-0710KL") (field (name "Manufacturer") "YAGEO(国巨)"))
      (libsource (lib "easyedapro") (part "RC0603FR-0710KL"))
    )
    (comp (ref "R26")
      (value "10kΩ")
      (footprint "easyedapro:R0603")
      (fields (field (name "Manufacturer Part") "RC0603FR-0710KL") (field (name "Manufacturer") "YAGEO(国巨)"))
      (libsource (lib "easyedapro") (part "RC0603FR-0710KL"))
    )
    (comp (ref "R27")
      (value "10kΩ")
      (footprint "easyedapro:R0603")
      (fields (field (name "Manufacturer Part") "RC0603FR-0710KL") (field (name "Manufacturer") "YAGEO(国巨)"))
      (libsource (lib "easyedapro") (part "RC0603FR-0710KL"))
    )
    (comp (ref "R28")
      (value "10kΩ")
      (footprint "easyedapro:R0603")
      (fields (field (name "Manufacturer Part") "RC0603FR-0710KL") (field (name "Manufacturer") "YAGEO(国巨)"))
      (libsource (lib "easyedapro") (part "RC0603FR-0710KL"))
    )
    (comp (ref "R29")
      (value "10kΩ")
      (footprint "easyedapro:R0603")
      (fields (field (name "Manufacturer Part") "RC0603FR-0710KL") (field (name "Manufacturer") "YAGEO(国巨)"))
      (libsource (lib "easyedapro") (part "RC0603FR-0710KL"))
    )
    (comp (ref "R30")
      (value "10kΩ")
      (footprint "easyedapro:R0603")
      (fields (field (name "Manufacturer Part") "RC0603FR-0710KL") (field (name "Manufacturer") "YAGEO(国巨)"))
      (libsource (lib "easyedapro") (part "RC0603FR-0710KL"))
    )
    (comp (ref "R31")
      (value "10kΩ")
      (footprint "easyedapro:R0603")
      (fields (field (name "Manufacturer Part") "RC0603FR-0710KL") (field (name "Manufacturer") "YAGEO(国巨)"))
      (libsource (lib "easyedapro") (part "RC0603FR-0710KL"))
    )
    (comp (ref "R32")
      (value "10kΩ")
      (footprint "easyedapro:R0603")
      (fields (field (name "Manufacturer Part") "RC0603FR-0710KL") (field (name "Manufacturer") "YAGEO(国巨)"))
      (libsource (lib "easyedapro") (part "RC0603FR-0710KL"))
    )
    (comp (ref "R33")
      (value "10kΩ")
      (footprint "easyedapro:R0603")
      (fields (field (name "Manufacturer Part") "RC0603FR-0710KL") (field (name "Manufacturer") "YAGEO(国巨)"))
      (libsource (lib "easyedapro") (part "RC0603FR-0710KL"))
    )
    (comp (ref "R34")
      (value "10kΩ")
      (footprint "easyedapro:R0603")
      (fields (field (name "Manufacturer Part") "RC0603FR-0710KL") (field (name "Manufacturer") "YAGEO(国巨)"))
      (libsource (lib "easyedapro") (part "RC0603FR-0710KL"))
    )
    (comp (ref "SONAR0")
      (value "ZX-XH2.54-4PZZ")
      (footprint "easyedapro:CONN-TH_4P-P2.50_4PIN")
      (fields (field (name "Manufacturer") "Megastar(兆星)"))
      (libsource (lib "easyedapro") (part "ZX-XH2.54-4PZZ"))
    )
    (comp (ref "SONAR1")
      (value "ZX-XH2.54-4PZZ")
      (footprint "easyedapro:CONN-TH_4P-P2.50_4PIN")
      (fields (field (name "Manufacturer") "Megastar(兆星)"))
      (libsource (lib "easyedapro") (part "ZX-XH2.54-4PZZ"))
    )
    (comp (ref "SONAR2")
      (value "ZX-XH2.54-4PZZ")
      (footprint "easyedapro:CONN-TH_4P-P2.50_4PIN")
      (fields (field (name "Manufacturer") "Megastar(兆星)"))
      (libsource (lib "easyedapro") (part "ZX-XH2.54-4PZZ"))
    )
    (comp (ref "SONAR3")
      (value "ZX-XH2.54-4PZZ")
      (footprint "easyedapro:CONN-TH_4P-P2.50_4PIN")
      (fields (field (name "Manufacturer") "Megastar(兆星)"))
      (libsource (lib "easyedapro") (part "ZX-XH2.54-4PZZ"))
    )
    (comp (ref "CN1")
      (value "ZX-XH2.54-3PZZ")
      (footprint "easyedapro:CONN-TH_3P-P2.54_2501S-3P")
      (fields (field (name "Manufacturer") "Megastar(兆星)"))
      (libsource (lib "easyedapro") (part "ZX-XH2.54-3PZZ"))
    )
    (comp (ref "CN2")
      (value "ZX-XH2.54-3PZZ")
      (footprint "easyedapro:CONN-TH_3P-P2.54_2501S-3P")
      (fields (field (name "Manufacturer") "Megastar(兆星)"))
      (libsource (lib "easyedapro") (part "ZX-XH2.54-3PZZ"))
    )
    (comp (ref "CN3")
      (value "ZX-XH2.54-3PZZ")
      (footprint "easyedapro:CONN-TH_3P-P2.54_2501S-3P")
      (fields (field (name "Manufacturer") "Megastar(兆星)"))
      (libsource (lib "easyedapro") (part "ZX-XH2.54-3PZZ"))
    )
    (comp (ref "CN50")
      (value "ZX-XH2.54-3PZZ")
      (footprint "easyedapro:CONN-TH_3P-P2.54_2501S-3P")
      (fields (field (name "Manufacturer") "Megastar(兆星)"))
      (libsource (lib "easyedapro") (part "ZX-XH2.54-3PZZ"))
    )
    (comp (ref "CN51")
      (value "ZX-XH2.54-3PZZ")
      (footprint "easyedapro:CONN-TH_3P-P2.54_2501S-3P")
      (fields (field (name "Manufacturer") "Megastar(兆星)"))
      (libsource (lib "easyedapro") (part "ZX-XH2.54-3PZZ"))
    )
    (comp (ref "CN52")
      (value "ZX-XH2.54-3PZZ")
      (footprint "easyedapro:CONN-TH_3P-P2.54_2501S-3P")
      (fields (field (name "Manufacturer") "Megastar(兆星)"))
      (libsource (lib "easyedapro") (part "ZX-XH2.54-3PZZ"))
    )
    (comp (ref "CN53")
      (value "ZX-XH2.54-3PZZ")
      (footprint "easyedapro:CONN-TH_3P-P2.54_2501S-3P")
      (fields (field (name "Manufacturer") "Megastar(兆星)"))
      (libsource (lib "easyedapro") (part "ZX-XH2.54-3PZZ"))
    )
    (comp (ref "CN54")
      (value "ZX-XH2.54-3PZZ")
      (footprint "easyedapro:CONN-TH_3P-P2.54_2501S-3P")
      (fields (field (name "Manufacturer") "Megastar(兆星)"))
      (libsource (lib "easyedapro") (part "ZX-XH2.54-3PZZ"))
    )
    (comp (ref "H1")
      (value "PZ254V-11-03P")
      (footprint "easyedapro:HDR-TH_3P-P2.54-V-M")
      (fields (field (name "Manufacturer") "XFCN(兴飞)"))
      (libsource (lib "easyedapro") (part "PZ254V-11-03P_C2937625"))
    )
    (comp (ref "P2")
      (value "WJ127-5.0-2P")
      (footprint "easyedapro:CONN-TH_2P-P5.00_CPC3703CTR")
      (fields (field (name "Manufacturer") "KANGNEX(康奈克斯电气)"))
      (libsource (lib "easyedapro") (part "WJ127-5.0-2P"))
    )
    (comp (ref "Q13")
      (value "BSS138")
      (footprint "easyedapro:SOT-23-3_L2.9-W1.6-P1.90-LS2.8-BR")
      (fields (field (name "Manufacturer") "TECH PUBLIC(台舟)"))
      (libsource (lib "easyedapro") (part "BSS138_C18212695"))
    )
    (comp (ref "Q14")
      (value "BSS138")
      (footprint "easyedapro:SOT-23-3_L2.9-W1.6-P1.90-LS2.8-BR")
      (fields (field (name "Manufacturer") "TECH PUBLIC(台舟)"))
      (libsource (lib "easyedapro") (part "BSS138_C18212695"))
    )
    (comp (ref "Q15")
      (value "BSS138")
      (footprint "easyedapro:SOT-23-3_L2.9-W1.6-P1.90-LS2.8-BR")
      (fields (field (name "Manufacturer") "TECH PUBLIC(台舟)"))
      (libsource (lib "easyedapro") (part "BSS138_C18212695"))
    )
    (comp (ref "Q16")
      (value "BSS138")
      (footprint "easyedapro:SOT-23-3_L2.9-W1.6-P1.90-LS2.8-BR")
      (fields (field (name "Manufacturer") "TECH PUBLIC(台舟)"))
      (libsource (lib "easyedapro") (part "BSS138_C18212695"))
    )
  )
  (nets
    (net (code "1") (name "3.3V") (class "Default")
      (node (ref "CN10") (pin "1") (pinfunction "1_1") (pintype "unspecified"))
      (node (ref "CN11") (pin "1") (pinfunction "1_1") (pintype "unspecified"))
      (node (ref "CN12") (pin "1") (pinfunction "1_1") (pintype "unspecified"))
      (node (ref "CN13") (pin "1") (pinfunction "1_1") (pintype "unspecified"))
      (node (ref "CN14") (pin "1") (pinfunction "1_1") (pintype "unspecified"))
      (node (ref "CN15") (pin "1") (pinfunction "1_1") (pintype "unspecified"))
      (node (ref "CN16") (pin "1") (pinfunction "1_1") (pintype "unspecified"))
      (node (ref "CN17") (pin "1") (pinfunction "1_1") (pintype "unspecified"))
      (node (ref "CN18") (pin "1") (pinfunction "1_1") (pintype "unspecified"))
      (node (ref "CN19") (pin "1") (pinfunction "1_1") (pintype "unspecified"))
      (node (ref "CN20") (pin "1") (pinfunction "1_1") (pintype "unspecified"))
      (node (ref "CN21") (pin "1") (pinfunction "1_1") (pintype "unspecified"))
      (node (ref "CN56") (pin "1") (pinfunction "1_1") (pintype "unspecified"))
      (node (ref "CN57") (pin "1") (pinfunction "1_1") (pintype "unspecified"))
      (node (ref "CN58") (pin "1") (pinfunction "1_1") (pintype "unspecified"))
      (node (ref "CN59") (pin "1") (pinfunction "1_1") (pintype "unspecified"))
      (node (ref "CN60") (pin "1") (pinfunction "1_1") (pintype "unspecified"))
      (node (ref "CN61") (pin "1") (pinfunction "1_1") (pintype "unspecified"))
      (node (ref "CN62") (pin "1") (pinfunction "1_1") (pintype "unspecified"))
      (node (ref "CN63") (pin "1") (pinfunction "1_1") (pintype "unspecified"))
      (node (ref "Q1") (pin "1") (pinfunction "G_1") (pintype "unspecified"))
      (node (ref "Q2") (pin "1") (pinfunction "G_1") (pintype "unspecified"))
      (node (ref "Q3") (pin "1") (pinfunction "G_1") (pintype "unspecified"))
      (node (ref "Q4") (pin "1") (pinfunction "G_1") (pintype "unspecified"))
      (node (ref "Q5") (pin "1") (pinfunction "G_1") (pintype "unspecified"))
      (node (ref "Q6") (pin "1") (pinfunction "G_1") (pintype "unspecified"))
      (node (ref "Q7") (pin "1") (pinfunction "G_1") (pintype "unspecified"))
      (node (ref "Q8") (pin "1") (pinfunction "G_1") (pintype "unspecified"))
      (node (ref "R1") (pin "1") (pinfunction "1_1") (pintype "input"))
      (node (ref "R10") (pin "2") (pinfunction "2_2") (pintype "input"))
      (node (ref "R11") (pin "2") (pinfunction "2_2") (pintype "input"))
      (node (ref "R12") (pin "2") (pinfunction "2_2") (pintype "input"))
      (node (ref "R13") (pin "2") (pinfunction "2_2") (pintype "input"))
      (node (ref "R14") (pin "2") (pinfunction "2_2") (pintype "input"))
      (node (ref "R15") (pin "2") (pinfunction "2_2") (pintype "input"))
      (node (ref "R16") (pin "2") (pinfunction "2_2") (pintype "input"))
      (node (ref "R17") (pin "2") (pinfunction "2_2") (pintype "input"))
      (node (ref "R18") (pin "2") (pinfunction "2_2") (pintype "input"))
      (node (ref "R2") (pin "1") (pinfunction "1_1") (pintype "input"))
      (node (ref "R20") (pin "1") (pinfunction "1_1") (pintype "input"))
      (node (ref "R22") (pin "2") (pinfunction "2_2") (pintype "input"))
      (node (ref "R24") (pin "1") (pinfunction "1_1") (pintype "input"))
      (node (ref "R26") (pin "2") (pinfunction "2_2") (pintype "input"))
      (node (ref "R28") (pin "1") (pinfunction "1_1") (pintype "input"))
      (node (ref "R3") (pin "1") (pinfunction "1_1") (pintype "input"))
      (node (ref "R30") (pin "2") (pinfunction "2_2") (pintype "input"))
      (node (ref "R32") (pin "1") (pinfunction "1_1") (pintype "input"))
      (node (ref "R34") (pin "2") (pinfunction "2_2") (pintype "input"))
      (node (ref "R4") (pin "1") (pinfunction "1_1") (pintype "input"))
      (node (ref "R5") (pin "1") (pinfunction "1_1") (pintype "input"))
      (node (ref "R6") (pin "1") (pinfunction "1_1") (pintype "input"))
      (node (ref "R7") (pin "1") (pinfunction "1_1") (pintype "input"))
      (node (ref "R8") (pin "1") (pinfunction "1_1") (pintype "input"))
      (node (ref "R9") (pin "2") (pinfunction "2_2") (pintype "input"))
      (node (ref "U1") (pin "15") (pinfunction "3.3V_15") (pintype "unspecified"))
      (node (ref "U1") (pin "46") (pinfunction "3.3V_46") (pintype "unspecified"))
      (node (ref "U2") (pin "24") (pinfunction "VCC_24") (pintype "unspecified"))
      (node (ref "U5") (pin "1") (pinfunction "1_1") (pintype "unspecified"))
      (node (ref "U6") (pin "1") (pinfunction "1_1") (pintype "unspecified"))
    )
    (net (code "2") (name "5V") (class "Default")
      (node (ref "CN1") (pin "3") (pinfunction "3_3") (pintype "unspecified"))
      (node (ref "CN2") (pin "3") (pinfunction "3_3") (pintype "unspecified"))
      (node (ref "CN3") (pin "3") (pinfunction "3_3") (pintype "unspecified"))
      (node (ref "CN54") (pin "3") (pinfunction "3_3") (pintype "unspecified"))
      (node (ref "H1") (pin "1") (pinfunction "1_1") (pintype "unspecified"))
      (node (ref "P1") (pin "2") (pinfunction "2_2") (pintype "input"))
      (node (ref "R19") (pin "1") (pinfunction "1_1") (pintype "input"))
      (node (ref "R21") (pin "2") (pinfunction "2_2") (pintype "input"))
      (node (ref "R23") (pin "1") (pinfunction "1_1") (pintype "input"))
      (node (ref "R25") (pin "2") (pinfunction "2_2") (pintype "input"))
      (node (ref "R27") (pin "1") (pinfunction "1_1") (pintype "input"))
      (node (ref "R29") (pin "2") (pinfunction "2_2") (pintype "input"))
      (node (ref "R31") (pin "1") (pinfunction "1_1") (pintype "input"))
      (node (ref "R33") (pin "2") (pinfunction "2_2") (pintype "input"))
      (node (ref "SONAR0") (pin "1") (pinfunction "1_1") (pintype "unspecified"))
      (node (ref "SONAR1") (pin "1") (pinfunction "1_1") (pintype "unspecified"))
      (node (ref "SONAR2") (pin "1") (pinfunction "1_1") (pintype "unspecified"))
      (node (ref "SONAR3") (pin "1") (pinfunction "1_1") (pintype "unspecified"))
      (node (ref "U1") (pin "48") (pinfunction "VIN_48") (pintype "unspecified"))
      (node (ref "U4") (pin "1") (pinfunction "1_1") (pintype "unspecified"))
      (node (ref "U8") (pin "1") (pinfunction "1_1") (pintype "unspecified"))
    )
    (net (code "3") (name "A10") (class "Default")
      (node (ref "CN63") (pin "3") (pinfunction "3_3") (pintype "unspecified"))
      (node (ref "U1") (pin "16") (pinfunction "SCL2/TX6/A10_16") (pintype "unspecified"))
    )
    (net (code "4") (name "A11") (class "Default")
      (node (ref "CN62") (pin "3") (pinfunction "3_3") (pintype "unspecified"))
      (node (ref "U1") (pin "17") (pinfunction "SDA2/RX6/A11_17") (pintype "unspecified"))
    )
    (net (code "5") (name "A12") (class "Default")
      (node (ref "CN61") (pin "3") (pinfunction "3_3") (pintype "unspecified"))
      (node (ref "U1") (pin "18") (pinfunction "MOSI1/A12_18") (pintype "unspecified"))
    )
    (net (code "6") (name "A13") (class "Default")
      (node (ref "CN60") (pin "3") (pinfunction "3_3") (pintype "unspecified"))
      (node (ref "U1") (pin "19") (pinfunction "SCK1/A13_19") (pintype "unspecified"))
    )
    (net (code "7") (name "A14") (class "Default")
      (node (ref "CN59") (pin "3") (pinfunction "3_3") (pintype "unspecified"))
      (node (ref "U1") (pin "30") (pinfunction "INN/CS1/A14_30") (pintype "unspecified"))
    )
    (net (code "8") (name "A15") (class "Default")
      (node (ref "CN58") (pin "3") (pinfunction "3_3") (pintype "unspecified"))
      (node (ref "U1") (pin "31") (pinfunction "OUT1A/MISO1/A15_31") (pintype "unspecified"))
    )
    (net (code "9") (name "A16") (class "Default")
      (node (ref "CN57") (pin "3") (pinfunction "3_3") (pintype "unspecified"))
      (node (ref "U1") (pin "32") (pinfunction "A16_32") (pintype "unspecified"))
    )
    (net (code "10") (name "A17") (class "Default")
      (node (ref "CN56") (pin "3") (pinfunction "3_3") (pintype "unspecified"))
      (node (ref "U1") (pin "33") (pinfunction "A17_33") (pintype "unspecified"))
    )
    (net (code "11") (name "BCLK2") (class "Default")
      (node (ref "CN50") (pin "3") (pinfunction "3_3") (pintype "unspecified"))
      (node (ref "U1") (pin "6") (pinfunction "BCLK2_6") (pintype "unspecified"))
    )
    (net (code "12") (name "CRX1") (class "Default")
      (node (ref "CN10") (pin "3") (pinfunction "3_3") (pintype "unspecified"))
      (node (ref "U1") (pin "45") (pinfunction "CRX1/A9_45") (pintype "unspecified"))
    )
    (net (code "13") (name "CRX3") (class "Default")
      (node (ref "U1") (pin "22") (pinfunction "CRX3_22") (pintype "unspecified"))
      (node (ref "U5") (pin "5") (pinfunction "5_5") (pintype "unspecified"))
    )
    (net (code "14") (name "CS") (class "Default")
      (node (ref "U1") (pin "12") (pinfunction "MQSR/CS_12") (pintype "unspecified"))
      (node (ref "U4") (pin "6") (pinfunction "6_6") (pintype "unspecified"))
    )
    (net (code "15") (name "CTX1") (class "Default")
      (node (ref "CN10") (pin "4") (pinfunction "4_4") (pintype "unspecified"))
      (node (ref "U1") (pin "44") (pinfunction "CTX1/A8_44") (pintype "unspecified"))
    )
    (net (code "16") (name "CTX3") (class "Default")
      (node (ref "U1") (pin "23") (pinfunction "CTX3_23") (pintype "unspecified"))
      (node (ref "U6") (pin "5") (pinfunction "5_5") (pintype "unspecified"))
    )
    (net (code "17") (name "ECHO0") (class "Default")
      (node (ref "Q2") (pin "3") (pinfunction "D_3") (pintype "unspecified"))
      (node (ref "R22") (pin "1") (pinfunction "1_1") (pintype "input"))
      (node (ref "U1") (pin "25") (pinfunction "MCLK2_25") (pintype "unspecified"))
    )
    (net (code "18") (name "ECHO1") (class "Default")
      (node (ref "Q4") (pin "3") (pinfunction "D_3") (pintype "unspecified"))
      (node (ref "R26") (pin "1") (pinfunction "1_1") (pintype "input"))
      (node (ref "U1") (pin "27") (pinfunction "TX8_27") (pintype "unspecified"))
    )
    (net (code "19") (name "ECHO2") (class "Default")
      (node (ref "Q6") (pin "3") (pinfunction "D_3") (pintype "unspecified"))
      (node (ref "R30") (pin "1") (pinfunction "1_1") (pintype "input"))
      (node (ref "U1") (pin "29") (pinfunction "CS_29") (pintype "unspecified"))
    )
    (net (code "20") (name "ECHO3") (class "Default")
      (node (ref "Q8") (pin "3") (pinfunction "D_3") (pintype "unspecified"))
      (node (ref "R34") (pin "1") (pinfunction "1_1") (pintype "input"))
      (node (ref "U1") (pin "37") (pinfunction "RX3/A1_37") (pintype "unspecified"))
    )
    (net (code "21") (name "GND") (class "Default")
      (node (ref "CN1") (pin "2") (pinfunction "2_2") (pintype "unspecified"))
      (node (ref "CN10") (pin "2") (pinfunction "2_2") (pintype "unspecified"))
      (node (ref "CN11") (pin "2") (pinfunction "2_2") (pintype "unspecified"))
      (node (ref "CN12") (pin "2") (pinfunction "2_2") (pintype "unspecified"))
      (node (ref "CN13") (pin "2") (pinfunction "2_2") (pintype "unspecified"))
      (node (ref "CN14") (pin "2") (pinfunction "2_2") (pintype "unspecified"))
      (node (ref "CN15") (pin "2") (pinfunction "2_2") (pintype "unspecified"))
      (node (ref "CN16") (pin "2") (pinfunction "2_2") (pintype "unspecified"))
      (node (ref "CN17") (pin "2") (pinfunction "2_2") (pintype "unspecified"))
      (node (ref "CN18") (pin "2") (pinfunction "2_2") (pintype "unspecified"))
      (node (ref "CN19") (pin "2") (pinfunction "2_2") (pintype "unspecified"))
      (node (ref "CN2") (pin "2") (pinfunction "2_2") (pintype "unspecified"))
      (node (ref "CN20") (pin "2") (pinfunction "2_2") (pintype "unspecified"))
      (node (ref "CN21") (pin "2") (pinfunction "2_2") (pintype "unspecified"))
      (node (ref "CN3") (pin "2") (pinfunction "2_2") (pintype "unspecified"))
      (node (ref "CN50") (pin "2") (pinfunction "2_2") (pintype "unspecified"))
      (node (ref "CN51") (pin "2") (pinfunction "2_2") (pintype "unspecified"))
      (node (ref "CN52") (pin "2") (pinfunction "2_2") (pintype "unspecified"))
      (node (ref "CN53") (pin "2") (pinfunction "2_2") (pintype "unspecified"))
      (node (ref "CN54") (pin "2") (pinfunction "2_2") (pintype "unspecified"))
      (node (ref "CN56") (pin "2") (pinfunction "2_2") (pintype "unspecified"))
      (node (ref "CN57") (pin "2") (pinfunction "2_2") (pintype "unspecified"))
      (node (ref "CN58") (pin "2") (pinfunction "2_2") (pintype "unspecified"))
      (node (ref "CN59") (pin "2") (pinfunction "2_2") (pintype "unspecified"))
      (node (ref "CN60") (pin "2") (pinfunction "2_2") (pintype "unspecified"))
      (node (ref "CN61") (pin "2") (pinfunction "2_2") (pintype "unspecified"))
      (node (ref "CN62") (pin "2") (pinfunction "2_2") (pintype "unspecified"))
      (node (ref "CN63") (pin "2") (pinfunction "2_2") (pintype "unspecified"))
      (node (ref "P1") (pin "1") (pinfunction "1_1") (pintype "input"))
      (node (ref "P2") (pin "1") (pinfunction "1_1") (pintype "input"))
      (node (ref "Q13") (pin "2") (pinfunction "S_2") (pintype "unspecified"))
      (node (ref "Q14") (pin "2") (pinfunction "S_2") (pintype "unspecified"))
      (node (ref "Q15") (pin "2") (pinfunction "S_2") (pintype "unspecified"))
      (node (ref "Q16") (pin "2") (pinfunction "S_2") (pintype "unspecified"))
      (node (ref "SONAR0") (pin "2") (pinfunction "2_2") (pintype "unspecified"))
      (node (ref "SONAR1") (pin "2") (pinfunction "2_2") (pintype "unspecified"))
      (node (ref "SONAR2") (pin "2") (pinfunction "2_2") (pintype "unspecified"))
      (node (ref "SONAR3") (pin "2") (pinfunction "2_2") (pintype "unspecified"))
      (node (ref "U1") (pin "1") (pinfunction "GND_1") (pintype "unspecified"))
      (node (ref "U1") (pin "34") (pinfunction "GND_34") (pintype "unspecified"))
      (node (ref "U1") (pin "47") (pinfunction "GND_47") (pintype "unspecified"))
      (node (ref "U2") (pin "1") (pinfunction "A0_1") (pintype "unspecified"))
      (node (ref "U2") (pin "12") (pinfunction "GND_12") (pintype "unspecified"))
      (node (ref "U2") (pin "2") (pinfunction "A1_2") (pintype "unspecified"))
      (node (ref "U2") (pin "21") (pinfunction "A2_21") (pintype "unspecified"))
      (node (ref "U4") (pin "2") (pinfunction "2_2") (pintype "unspecified"))
      (node (ref "U5") (pin "2") (pinfunction "2_2") (pintype "unspecified"))
      (node (ref "U6") (pin "2") (pinfunction "2_2") (pintype "unspecified"))
      (node (ref "U8") (pin "2") (pinfunction "2_2") (pintype "unspecified"))
    )
    (net (code "22") (name "I2CRESET") (class "Default")
      (node (ref "U1") (pin "10") (pinfunction "IN1/TX2_10") (pintype "unspecified"))
      (node (ref "U2") (pin "3") (pinfunction "RESET#_3") (pintype "unspecified"))
    )
    (net (code "23") (name "IN2") (class "Default")
      (node (ref "CN51") (pin "3") (pinfunction "3_3") (pintype "unspecified"))
      (node (ref "U1") (pin "7") (pinfunction "IN2_7") (pintype "unspecified"))
    )
    (net (code "24") (name "LRCLK2") (class "Default")
      (node (ref "Q16") (pin "1") (pinfunction "G_1") (pintype "unspecified"))
      (node (ref "U1") (pin "5") (pinfunction "LRCLK2_5") (pintype "unspecified"))
    )
    (net (code "25") (name "MISO") (class "Default")
      (node (ref "U1") (pin "14") (pinfunction "MQSL/MISO_14") (pintype "unspecified"))
      (node (ref "U4") (pin "4") (pinfunction "4_4") (pintype "unspecified"))
      (node (ref "U8") (pin "4") (pinfunction "4_4") (pintype "unspecified"))
    )
    (net (code "26") (name "MOSI") (class "Default")
      (node (ref "U1") (pin "13") (pinfunction "CTX1/MOSI_13") (pintype "unspecified"))
      (node (ref "U4") (pin "3") (pinfunction "3_3") (pintype "unspecified"))
      (node (ref "U8") (pin "3") (pinfunction "3_3") (pintype "unspecified"))
    )
    (net (code "27") (name "Net-(CN50-Pad1)") (class "Default")
      (node (ref "CN50") (pin "1") (pinfunction "1_1") (pintype "unspecified"))
      (node (ref "CN51") (pin "1") (pinfunction "1_1") (pintype "unspecified"))
      (node (ref "CN52") (pin "1") (pinfunction "1_1") (pintype "unspecified"))
      (node (ref "CN53") (pin "1") (pinfunction "1_1") (pintype "unspecified"))
      (node (ref "H1") (pin "2") (pinfunction "2_2") (pintype "unspecified"))
    )
    (net (code "28") (name "Net-(H1-Pad3)") (class "Default")
      (node (ref "H1") (pin "3") (pinfunction "3_3") (pintype "unspecified"))
      (node (ref "P2") (pin "2") (pinfunction "2_2") (pintype "input"))
    )
    (net (code "29") (name "Net-(Q1-D)") (class "Default")
      (node (ref "Q1") (pin "3") (pinfunction "D_3") (pintype "unspecified"))
      (node (ref "R19") (pin "2") (pinfunction "2_2") (pintype "input"))
      (node (ref "SONAR0") (pin "3") (pinfunction "3_3") (pintype "unspecified"))
    )
    (net (code "30") (name "Net-(Q2-S)") (class "Default")
      (node (ref "Q2") (pin "2") (pinfunction "S_2") (pintype "unspecified"))
      (node (ref "R21") (pin "1") (pinfunction "1_1") (pintype "input"))
      (node (ref "SONAR0") (pin "4") (pinfunction "4_4") (pintype "unspecified"))
    )
    (net (code "31") (name "Net-(Q3-D)") (class "Default")
      (node (ref "Q3") (pin "3") (pinfunction "D_3") (pintype "unspecified"))
      (node (ref "R23") (pin "2") (pinfunction "2_2") (pintype "input"))
      (node (ref "SONAR1") (pin "3") (pinfunction "3_3") (pintype "unspecified"))
    )
    (net (code "32") (name "Net-(Q4-S)") (class "Default")
      (node (ref "Q4") (pin "2") (pinfunction "S_2") (pintype "unspecified"))
      (node (ref "R25") (pin "1") (pinfunction "1_1") (pintype "input"))
      (node (ref "SONAR1") (pin "4") (pinfunction "4_4") (pintype "unspecified"))
    )
    (net (code "33") (name "Net-(Q5-D)") (class "Default")
      (node (ref "Q5") (pin "3") (pinfunction "D_3") (pintype "unspecified"))
      (node (ref "R27") (pin "2") (pinfunction "2_2") (pintype "input"))
      (node (ref "SONAR2") (pin "3") (pinfunction "3_3") (pintype "unspecified"))
    )
    (net (code "34") (name "Net-(Q6-S)") (class "Default")
      (node (ref "Q6") (pin "2") (pinfunction "S_2") (pintype "unspecified"))
      (node (ref "R29") (pin "1") (pinfunction "1_1") (pintype "input"))
      (node (ref "SONAR2") (pin "4") (pinfunction "4_4") (pintype "unspecified"))
    )
    (net (code "35") (name "Net-(Q7-D)") (class "Default")
      (node (ref "Q7") (pin "3") (pinfunction "D_3") (pintype "unspecified"))
      (node (ref "R31") (pin "2") (pinfunction "2_2") (pintype "input"))
      (node (ref "SONAR3") (pin "3") (pinfunction "3_3") (pintype "unspecified"))
    )
    (net (code "36") (name "Net-(Q8-S)") (class "Default")
      (node (ref "Q8") (pin "2") (pinfunction "S_2") (pintype "unspecified"))
      (node (ref "R33") (pin "1") (pinfunction "1_1") (pintype "input"))
      (node (ref "SONAR3") (pin "4") (pinfunction "4_4") (pintype "unspecified"))
    )
    (net (code "37") (name "Net-(Q13-D)") (class "Default")
      (node (ref "CN3") (pin "1") (pinfunction "1_1") (pintype "unspecified"))
      (node (ref "Q13") (pin "3") (pinfunction "D_3") (pintype "unspecified"))
    )
    (net (code "38") (name "Net-(Q14-D)") (class "Default")
      (node (ref "CN54") (pin "1") (pinfunction "1_1") (pintype "unspecified"))
      (node (ref "Q14") (pin "3") (pinfunction "D_3") (pintype "unspecified"))
    )
    (net (code "39") (name "Net-(Q15-D)") (class "Default")
      (node (ref "CN2") (pin "1") (pinfunction "1_1") (pintype "unspecified"))
      (node (ref "Q15") (pin "3") (pinfunction "D_3") (pintype "unspecified"))
    )
    (net (code "40") (name "Net-(Q16-D)") (class "Default")
      (node (ref "CN1") (pin "1") (pinfunction "1_1") (pintype "unspecified"))
      (node (ref "Q16") (pin "3") (pinfunction "D_3") (pintype "unspecified"))
    )
    (net (code "41") (name "Net-(U2-SC0)") (class "Default")
      (node (ref "CN14") (pin "3") (pinfunction "3_3") (pintype "unspecified"))
      (node (ref "R2") (pin "2") (pinfunction "2_2") (pintype "input"))
      (node (ref "U2") (pin "5") (pinfunction "SC0_5") (pintype "unspecified"))
    )
    (net (code "42") (name "Net-(U2-SC1)") (class "Default")
      (node (ref "CN15") (pin "3") (pinfunction "3_3") (pintype "unspecified"))
      (node (ref "R4") (pin "2") (pinfunction "2_2") (pintype "input"))
      (node (ref "U2") (pin "7") (pinfunction "SC1_7") (pintype "unspecified"))
    )
    (net (code "43") (name "Net-(U2-SC2)") (class "Default")
      (node (ref "CN16") (pin "3") (pinfunction "3_3") (pintype "unspecified"))
      (node (ref "R6") (pin "2") (pinfunction "2_2") (pintype "input"))
      (node (ref "U2") (pin "9") (pinfunction "SC2_9") (pintype "unspecified"))
    )
    (net (code "44") (name "Net-(U2-SC3)") (class "Default")
      (node (ref "CN17") (pin "3") (pinfunction "3_3") (pintype "unspecified"))
      (node (ref "R8") (pin "2") (pinfunction "2_2") (pintype "input"))
      (node (ref "U2") (pin "11") (pinfunction "SC3_11") (pintype "unspecified"))
    )
    (net (code "45") (name "Net-(U2-SC4)") (class "Default")
      (node (ref "CN18") (pin "3") (pinfunction "3_3") (pintype "unspecified"))
      (node (ref "R15") (pin "1") (pinfunction "1_1") (pintype "input"))
      (node (ref "U2") (pin "14") (pinfunction "SC4_14") (pintype "unspecified"))
    )
    (net (code "46") (name "Net-(U2-SC5)") (class "Default")
      (node (ref "CN19") (pin "3") (pinfunction "3_3") (pintype "unspecified"))
      (node (ref "R13") (pin "1") (pinfunction "1_1") (pintype "input"))
      (node (ref "U2") (pin "16") (pinfunction "SC5_16") (pintype "unspecified"))
    )
    (net (code "47") (name "Net-(U2-SC6)") (class "Default")
      (node (ref "CN20") (pin "3") (pinfunction "3_3") (pintype "unspecified"))
      (node (ref "R11") (pin "1") (pinfunction "1_1") (pintype "input"))
      (node (ref "U2") (pin "18") (pinfunction "SC6_18") (pintype "unspecified"))
    )
    (net (code "48") (name "Net-(U2-SC7)") (class "Default")
      (node (ref "CN21") (pin "3") (pinfunction "3_3") (pintype "unspecified"))
      (node (ref "R9") (pin "1") (pinfunction "1_1") (pintype "input"))
      (node (ref "U2") (pin "20") (pinfunction "SC7_20") (pintype "unspecified"))
    )
    (net (code "49") (name "Net-(U2-SD0)") (class "Default")
      (node (ref "CN14") (pin "4") (pinfunction "4_4") (pintype "unspecified"))
      (node (ref "R1") (pin "2") (pinfunction "2_2") (pintype "input"))
      (node (ref "U2") (pin "4") (pinfunction "SD0_4") (pintype "unspecified"))
    )
    (net (code "50") (name "Net-(U2-SD1)") (class "Default")
      (node (ref "CN15") (pin "4") (pinfunction "4_4") (pintype "unspecified"))
      (node (ref "R3") (pin "2") (pinfunction "2_2") (pintype "input"))
      (node (ref "U2") (pin "6") (pinfunction "SD1_6") (pintype "unspecified"))
    )
    (net (code "51") (name "Net-(U2-SD2)") (class "Default")
      (node (ref "CN16") (pin "4") (pinfunction "4_4") (pintype "unspecified"))
      (node (ref "R5") (pin "2") (pinfunction "2_2") (pintype "input"))
      (node (ref "U2") (pin "8") (pinfunction "SD2_8") (pintype "unspecified"))
    )
    (net (code "52") (name "Net-(U2-SD3)") (class "Default")
      (node (ref "CN17") (pin "4") (pinfunction "4_4") (pintype "unspecified"))
      (node (ref "R7") (pin "2") (pinfunction "2_2") (pintype "input"))
      (node (ref "U2") (pin "10") (pinfunction "SD3_10") (pintype "unspecified"))
    )
    (net (code "53") (name "Net-(U2-SD4)") (class "Default")
      (node (ref "CN18") (pin "4") (pinfunction "4_4") (pintype "unspecified"))
      (node (ref "R16") (pin "1") (pinfunction "1_1") (pintype "input"))
      (node (ref "U2") (pin "13") (pinfunction "SD4_13") (pintype "unspecified"))
    )
    (net (code "54") (name "Net-(U2-SD5)") (class "Default")
      (node (ref "CN19") (pin "4") (pinfunction "4_4") (pintype "unspecified"))
      (node (ref "R14") (pin "1") (pinfunction "1_1") (pintype "input"))
      (node (ref "U2") (pin "15") (pinfunction "SD5_15") (pintype "unspecified"))
    )
    (net (code "55") (name "Net-(U2-SD6)") (class "Default")
      (node (ref "CN20") (pin "4") (pinfunction "4_4") (pintype "unspecified"))
      (node (ref "R12") (pin "1") (pinfunction "1_1") (pintype "input"))
      (node (ref "U2") (pin "17") (pinfunction "SD6_17") (pintype "unspecified"))
    )
    (net (code "56") (name "Net-(U2-SD7)") (class "Default")
      (node (ref "CN21") (pin "4") (pinfunction "4_4") (pintype "unspecified"))
      (node (ref "R10") (pin "1") (pinfunction "1_1") (pintype "input"))
      (node (ref "U2") (pin "19") (pinfunction "SD7_19") (pintype "unspecified"))
    )
    (net (code "57") (name "OUT1A") (class "Default")
      (node (ref "CN53") (pin "3") (pinfunction "3_3") (pintype "unspecified"))
      (node (ref "U1") (pin "9") (pinfunction "OUT1A/RX2_9") (pintype "unspecified"))
    )
    (net (code "58") (name "OUT1C") (class "Default")
      (node (ref "U1") (pin "11") (pinfunction "OUT1C_11") (pintype "unspecified"))
      (node (ref "U8") (pin "6") (pinfunction "6_6") (pintype "unspecified"))
    )
    (net (code "59") (name "OUT1D") (class "Default")
      (node (ref "CN52") (pin "3") (pinfunction "3_3") (pintype "unspecified"))
      (node (ref "U1") (pin "8") (pinfunction "OUT1D_8") (pintype "unspecified"))
    )
    (net (code "60") (name "OUT2") (class "Default")
      (node (ref "Q15") (pin "1") (pinfunction "G_1") (pintype "unspecified"))
      (node (ref "U1") (pin "4") (pinfunction "OUT2_4") (pintype "unspecified"))
    )
    (net (code "61") (name "RX1") (class "Default")
      (node (ref "Q13") (pin "1") (pinfunction "G_1") (pintype "unspecified"))
      (node (ref "U1") (pin "2") (pinfunction "CRX2/CS1/RX1_2") (pintype "unspecified"))
    )
    (net (code "62") (name "RX4") (class "Default")
      (node (ref "U1") (pin "38") (pinfunction "RX4/A2_38") (pintype "unspecified"))
      (node (ref "U6") (pin "3") (pinfunction "3_3") (pintype "unspecified"))
    )
    (net (code "63") (name "RX5") (class "Default")
      (node (ref "CN13") (pin "3") (pinfunction "3_3") (pintype "unspecified"))
      (node (ref "U1") (pin "43") (pinfunction "RX5/A7_43") (pintype "unspecified"))
    )
    (net (code "64") (name "RX7") (class "Default")
      (node (ref "U1") (pin "20") (pinfunction "RX7_20") (pintype "unspecified"))
      (node (ref "U5") (pin "3") (pinfunction "3_3") (pintype "unspecified"))
    )
    (net (code "65") (name "SCK") (class "Default")
      (node (ref "U1") (pin "35") (pinfunction "SCK_35") (pintype "unspecified"))
      (node (ref "U4") (pin "5") (pinfunction "5_5") (pintype "unspecified"))
      (node (ref "U8") (pin "5") (pinfunction "5_5") (pintype "unspecified"))
    )
    (net (code "66") (name "SCL") (class "Default")
      (node (ref "CN11") (pin "3") (pinfunction "3_3") (pintype "unspecified"))
      (node (ref "CN12") (pin "3") (pinfunction "3_3") (pintype "unspecified"))
      (node (ref "R17") (pin "1") (pinfunction "1_1") (pintype "input"))
      (node (ref "U1") (pin "41") (pinfunction "A5_41") (pintype "unspecified"))
      (node (ref "U2") (pin "22") (pinfunction "SCL_22") (pintype "unspecified"))
    )
    (net (code "67") (name "SDA") (class "Default")
      (node (ref "CN11") (pin "4") (pinfunction "4_4") (pintype "unspecified"))
      (node (ref "CN12") (pin "4") (pinfunction "4_4") (pintype "unspecified"))
      (node (ref "R18") (pin "1") (pinfunction "1_1") (pintype "input"))
      (node (ref "U1") (pin "40") (pinfunction "A4_40") (pintype "unspecified"))
      (node (ref "U2") (pin "23") (pinfunction "SDA_23") (pintype "unspecified"))
    )
    (net (code "68") (name "TRIG0") (class "Default")
      (node (ref "Q1") (pin "2") (pinfunction "S_2") (pintype "unspecified"))
      (node (ref "R20") (pin "2") (pinfunction "2_2") (pintype "input"))
      (node (ref "U1") (pin "24") (pinfunction "OUT1B_24") (pintype "unspecified"))
    )
    (net (code "69") (name "TRIG1") (class "Default")
      (node (ref "Q3") (pin "2") (pinfunction "S_2") (pintype "unspecified"))
      (node (ref "R24") (pin "2") (pinfunction "2_2") (pintype "input"))
      (node (ref "U1") (pin "26") (pinfunction "RX8_26") (pintype "unspecified"))
    )
    (net (code "70") (name "TRIG2") (class "Default")
      (node (ref "Q5") (pin "2") (pinfunction "S_2") (pintype "unspecified"))
      (node (ref "R28") (pin "2") (pinfunction "2_2") (pintype "input"))
      (node (ref "U1") (pin "28") (pinfunction "CS_28") (pintype "unspecified"))
    )
    (net (code "71") (name "TRIG3") (class "Default")
      (node (ref "Q7") (pin "2") (pinfunction "S_2") (pintype "unspecified"))
      (node (ref "R32") (pin "2") (pinfunction "2_2") (pintype "input"))
      (node (ref "U1") (pin "36") (pinfunction "TX3/A0_36") (pintype "unspecified"))
    )
    (net (code "72") (name "TX1") (class "Default")
      (node (ref "Q14") (pin "1") (pinfunction "G_1") (pintype "unspecified"))
      (node (ref "U1") (pin "3") (pinfunction "CTX2/MISO1/TX1_3") (pintype "unspecified"))
    )
    (net (code "73") (name "TX4") (class "Default")
      (node (ref "U1") (pin "39") (pinfunction "TX4/A3_39") (pintype "unspecified"))
      (node (ref "U6") (pin "4") (pinfunction "4_4") (pintype "unspecified"))
    )
    (net (code "74") (name "TX5") (class "Default")
      (node (ref "CN13") (pin "4") (pinfunction "4_4") (pintype "unspecified"))
      (node (ref "U1") (pin "42") (pinfunction "TX5/A6_42") (pintype "unspecified"))
    )
    (net (code "75") (name "TX7") (class "Default")
      (node (ref "U1") (pin "21") (pinfunction "TX7_21") (pintype "unspecified"))
      (node (ref "U5") (pin "4") (pinfunction "4_4") (pintype "unspecified"))
    )
  )
)
